# NB-IoT-ideaboard-v2_0.net
KiCad netlist of a schematic drawn in EAGLE
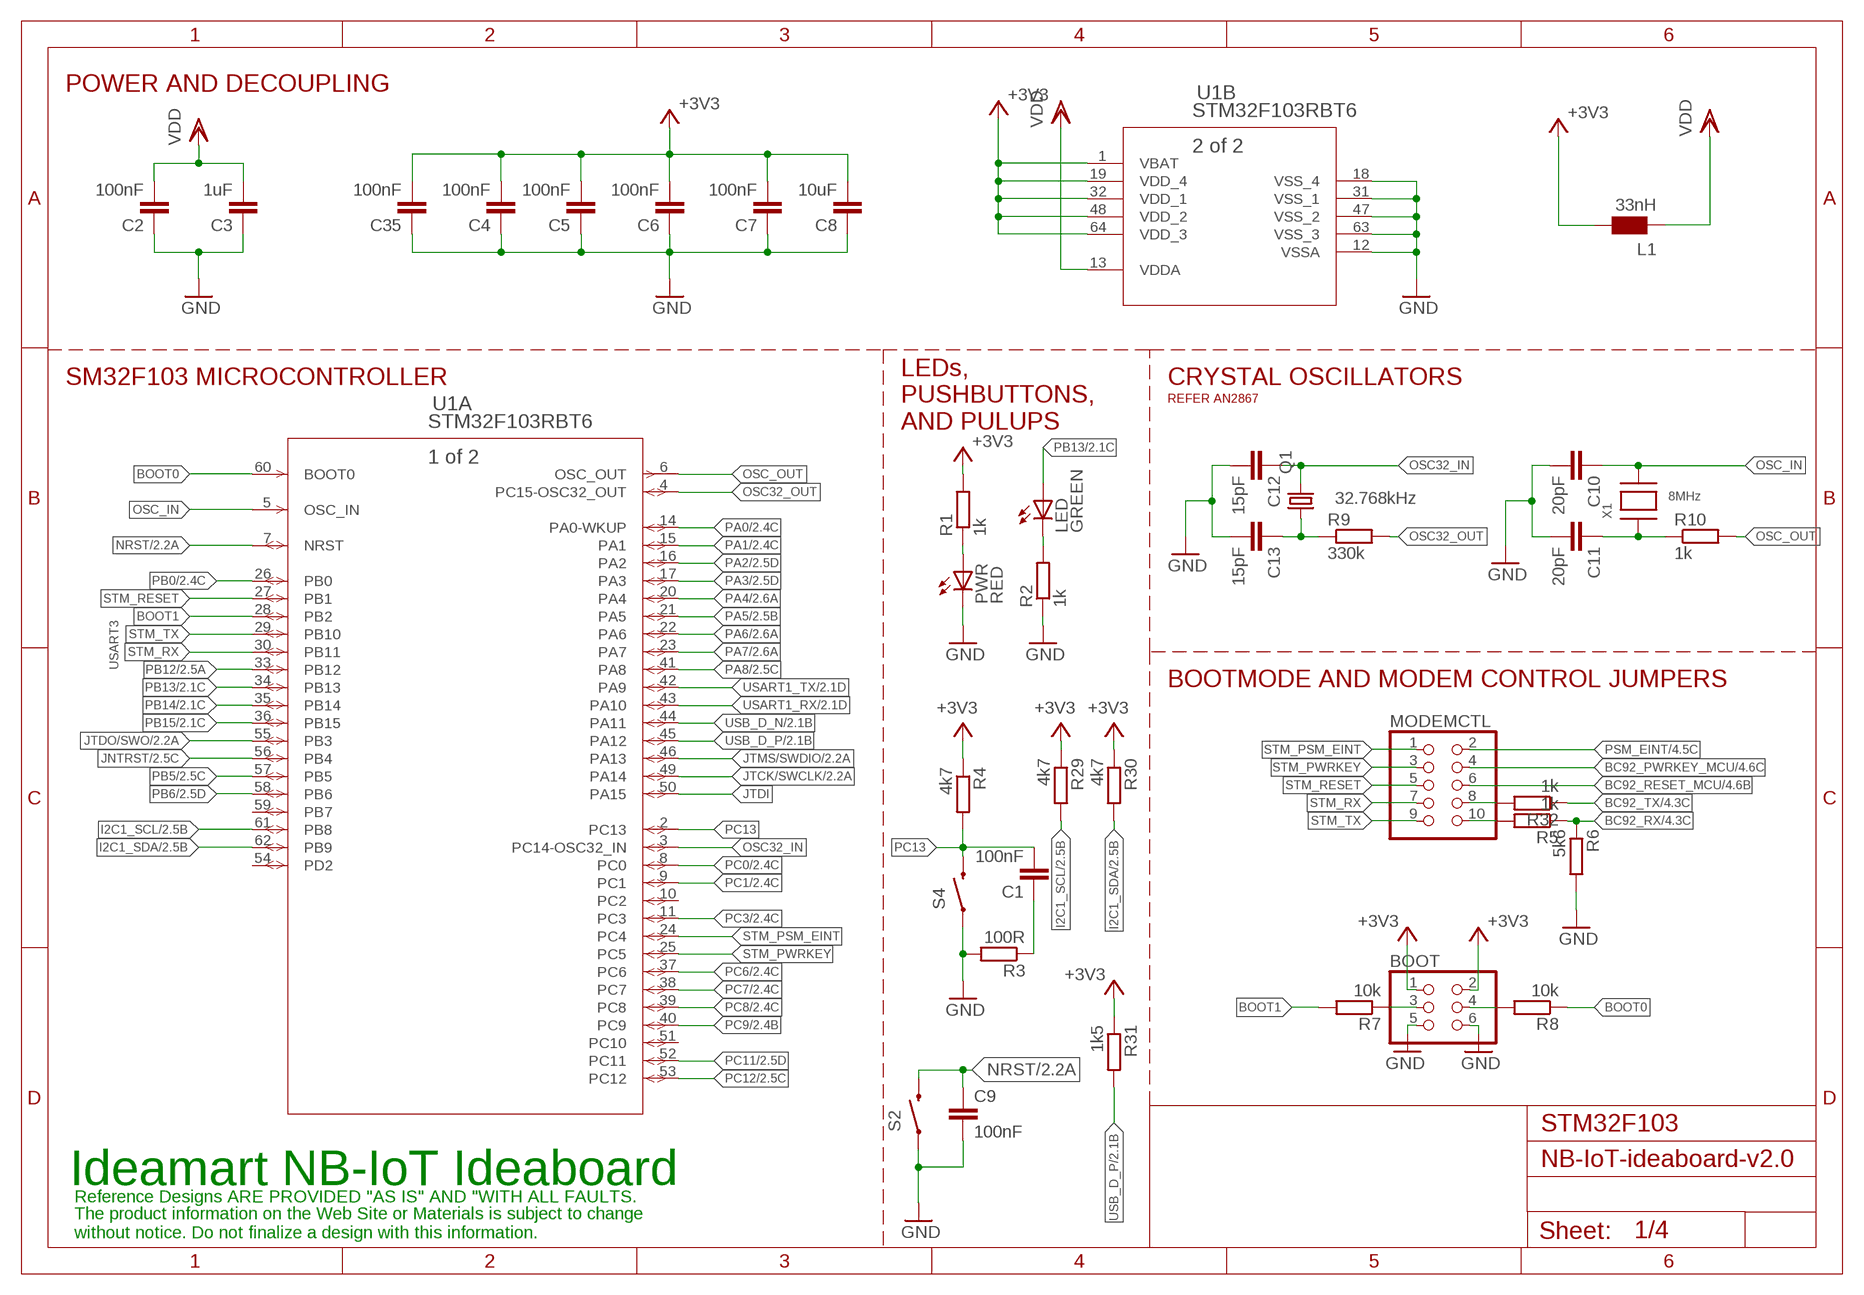
[diagram p0: schematic, sheet 1]
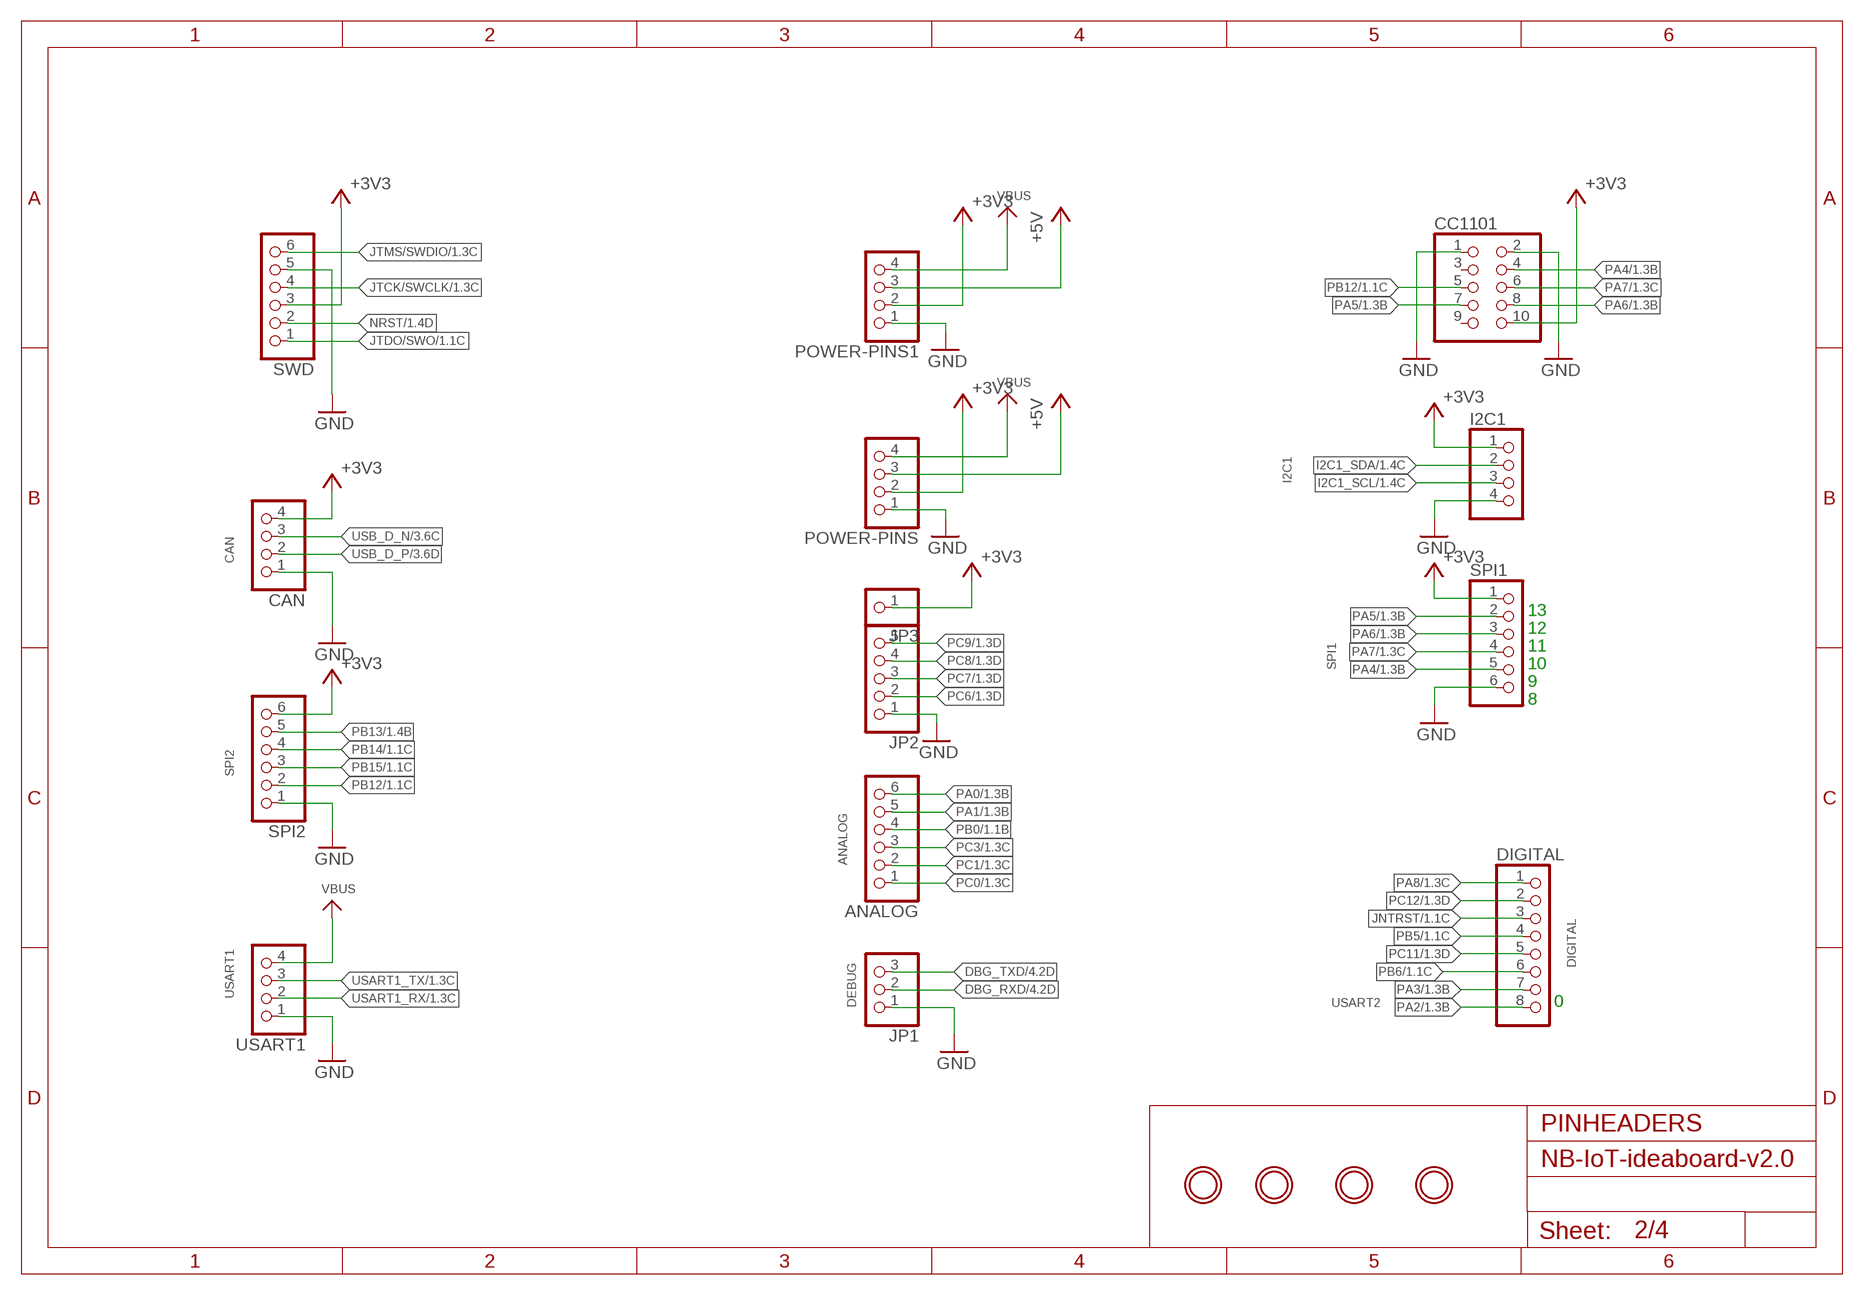
[diagram p1: schematic, sheet 2]
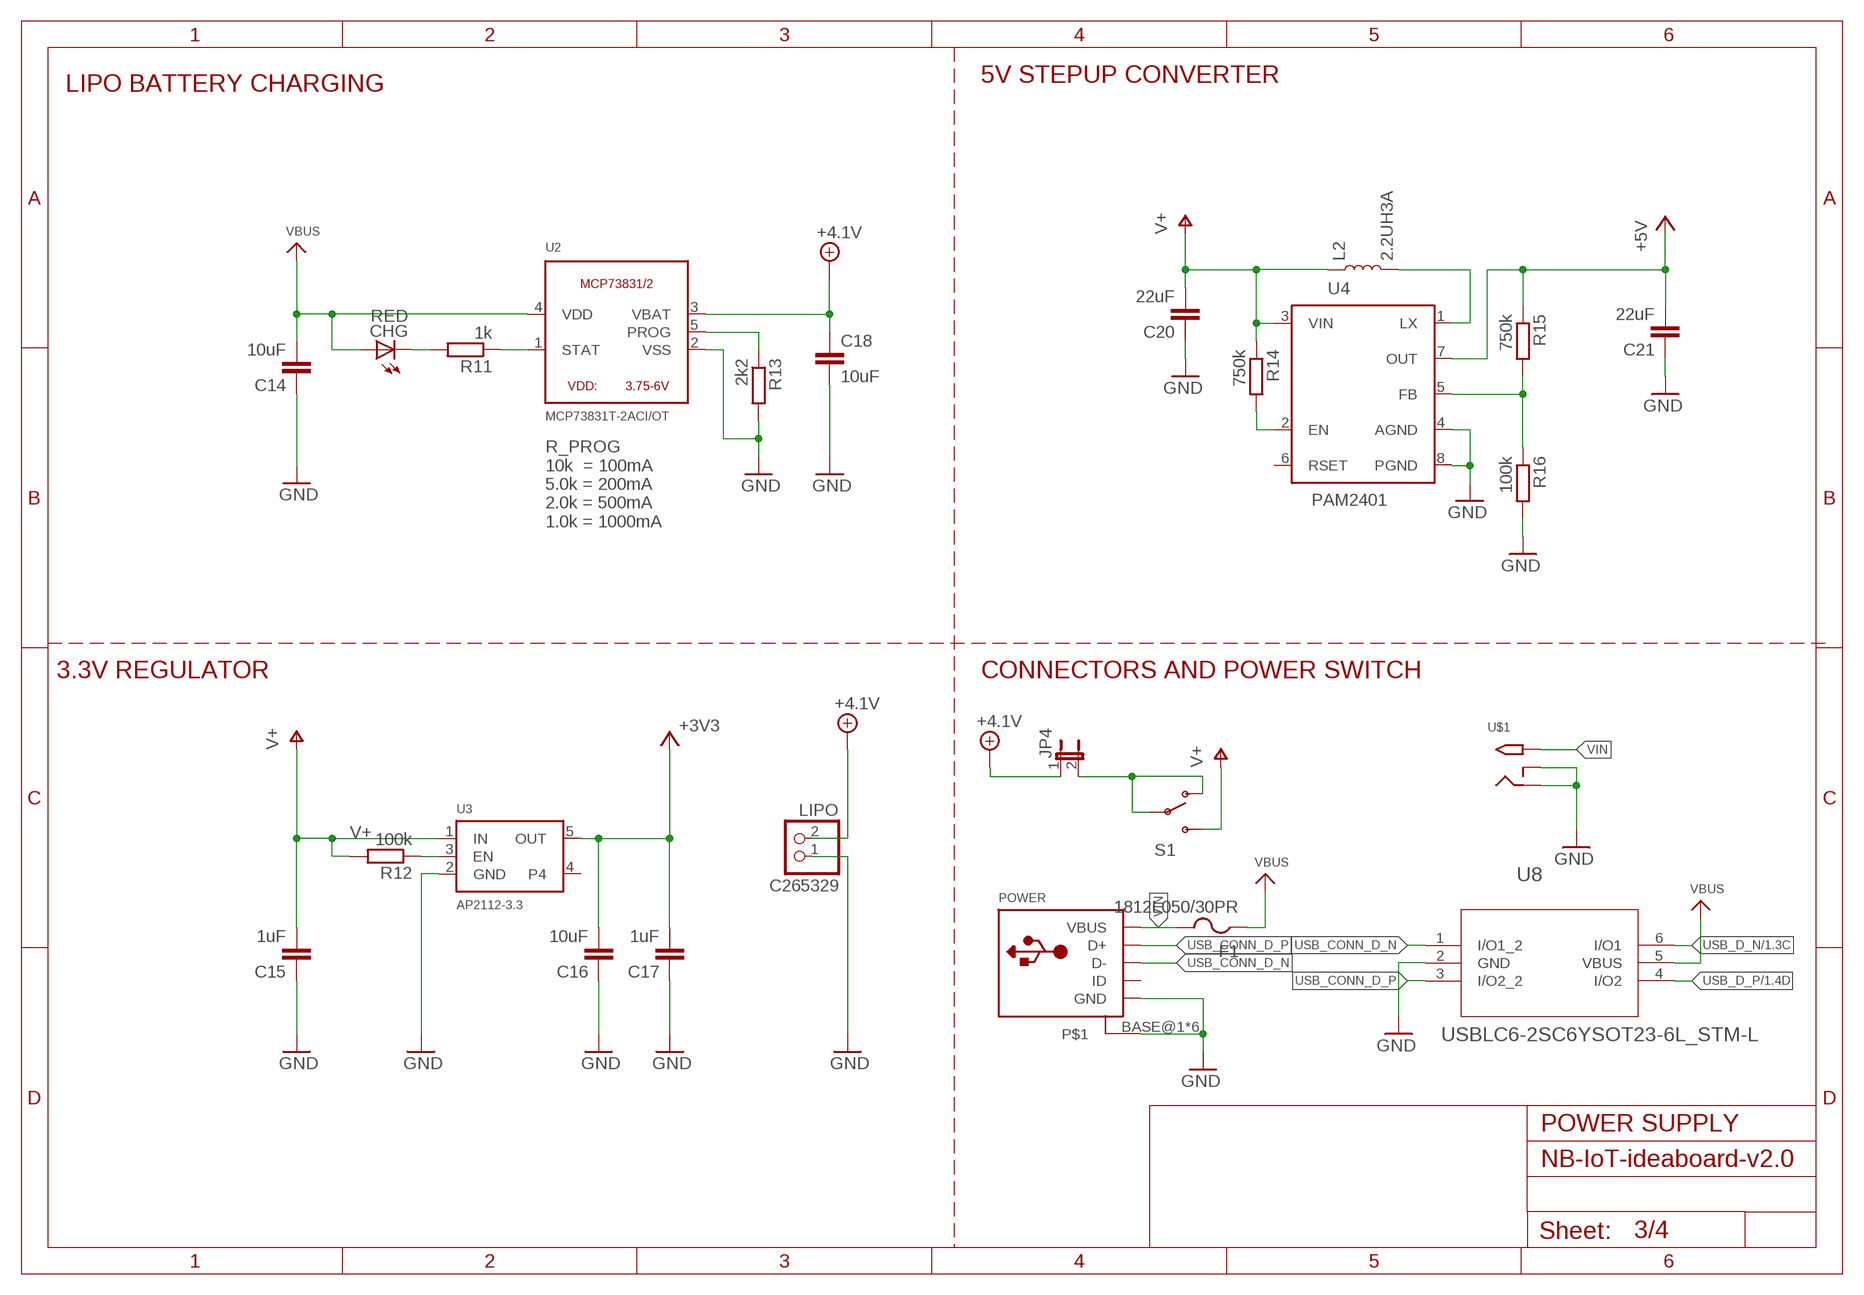
[diagram p2: schematic, sheet 3]
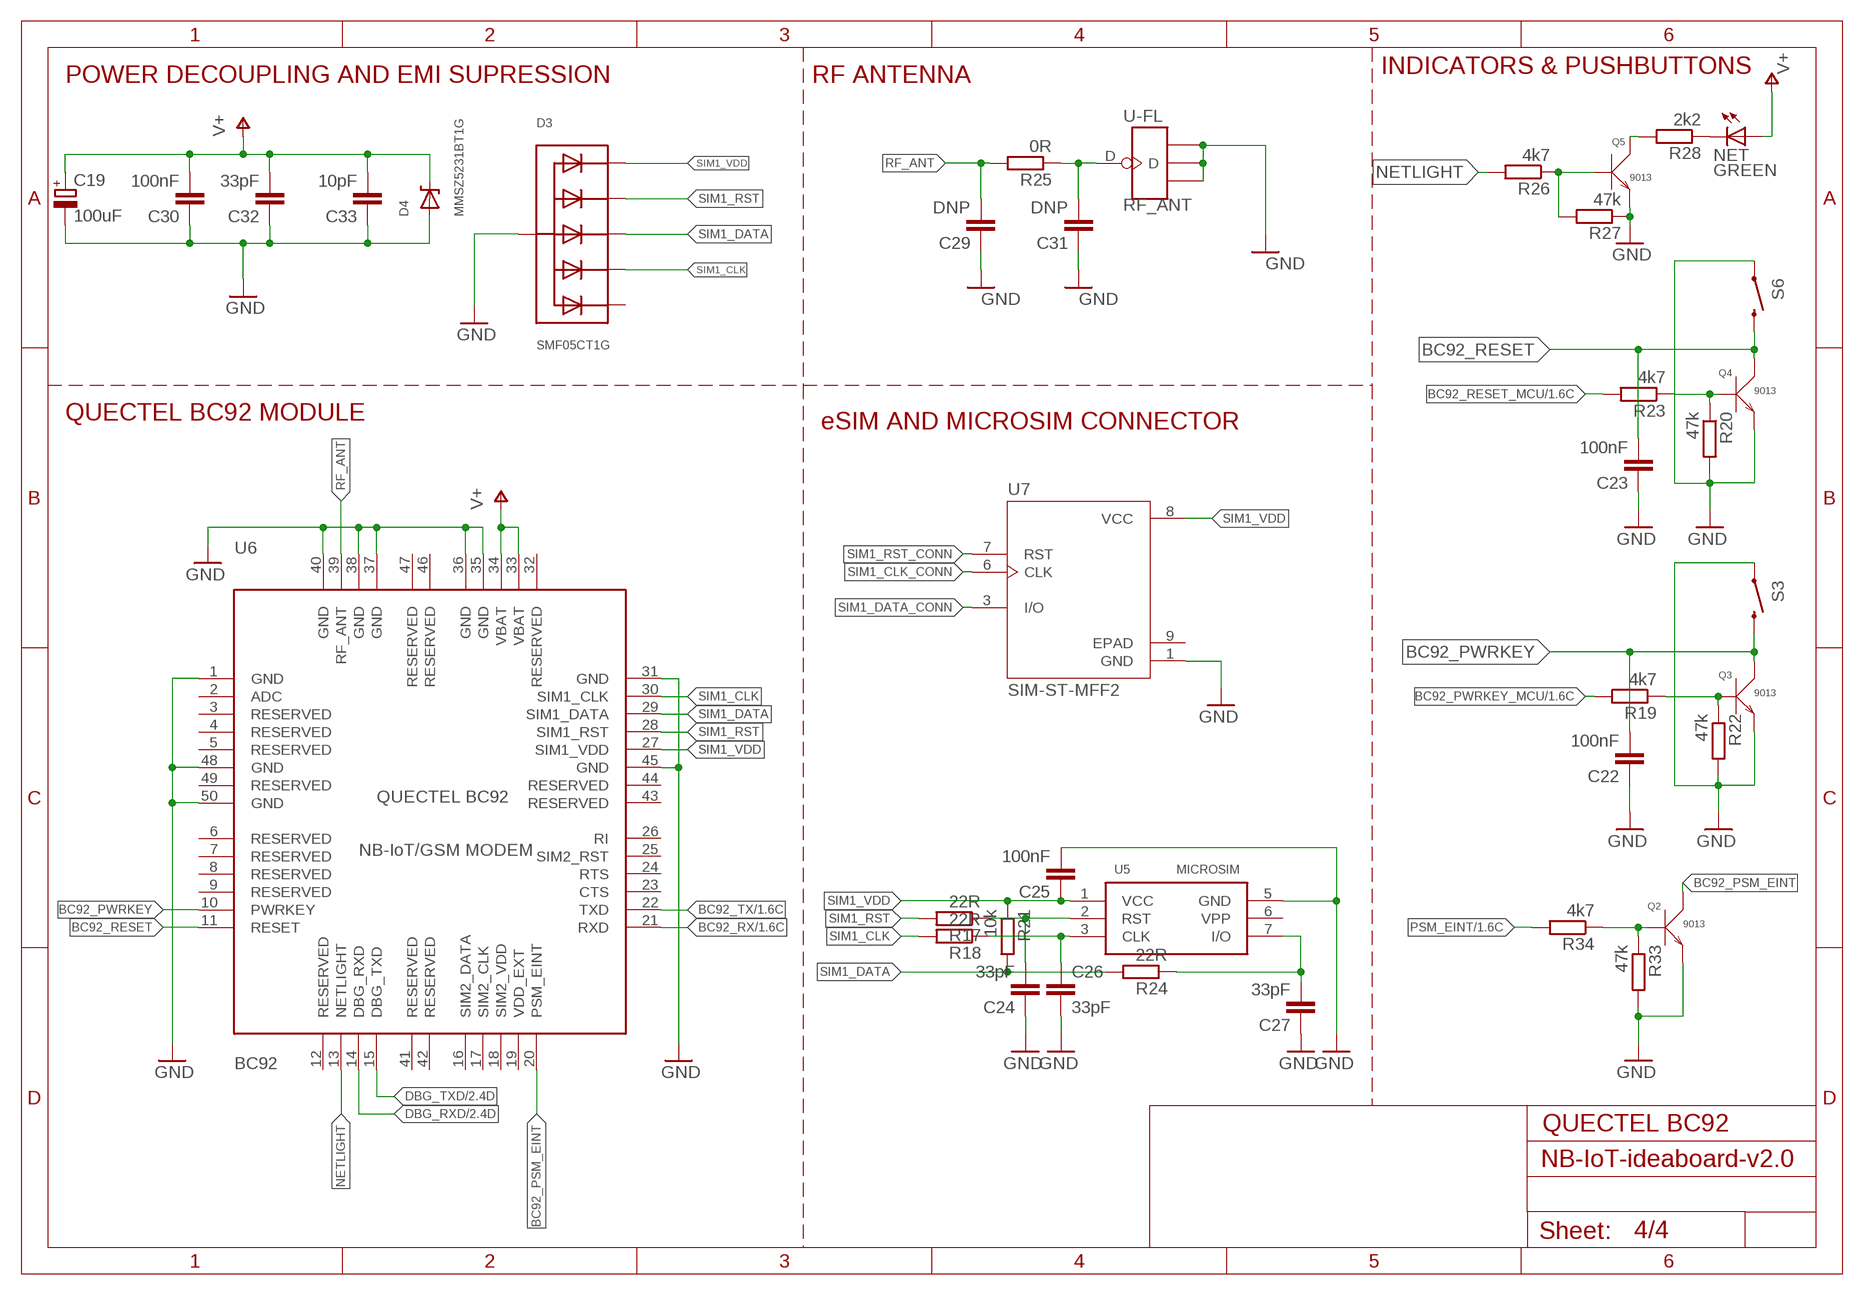
[diagram p3: schematic, sheet 4]

(export (version "E")
  (design (tool "Eeschema 10.0.6"))
  (components
    (comp (ref "$H1")
      (value "MOUNTINGHOLE3.0THIN")
      (footprint "eagle-import:MOUNTINGHOLE_3.0_PLATEDTHIN")
      (libsource (lib "eagle-import") (part "MOUNTINGHOLE3.0THIN"))
    )
    (comp (ref "$H2")
      (value "MOUNTINGHOLE3.0THIN")
      (footprint "eagle-import:MOUNTINGHOLE_3.0_PLATEDTHIN")
      (libsource (lib "eagle-import") (part "MOUNTINGHOLE3.0THIN"))
    )
    (comp (ref "$H3")
      (value "MOUNTINGHOLE3.0THIN")
      (footprint "eagle-import:MOUNTINGHOLE_3.0_PLATEDTHIN")
      (libsource (lib "eagle-import") (part "MOUNTINGHOLE3.0THIN"))
    )
    (comp (ref "$H4")
      (value "MOUNTINGHOLE3.0THIN")
      (footprint "eagle-import:MOUNTINGHOLE_3.0_PLATEDTHIN")
      (libsource (lib "eagle-import") (part "MOUNTINGHOLE3.0THIN"))
    )
    (comp (ref "ANALOG")
      (value "PINHD-1X06_2.54-S")
      (footprint "eagle-import:1X06-S")
      (libsource (lib "eagle-import") (part "PINHD-1X06_2.54-S"))
    )
    (comp (ref "CAN")
      (value "PINHD-1X04_2.54-S")
      (footprint "eagle-import:1X04-S")
      (libsource (lib "eagle-import") (part "PINHD-1X04_2.54-S"))
    )
    (comp (ref "CC1101")
      (value "PINHD-2X05_2.54")
      (footprint "eagle-import:2X05")
      (libsource (lib "eagle-import") (part "PINHD-2X05_2.54"))
    )
    (comp (ref "DIGITAL")
      (value "PINHD-1X08_2.54-S")
      (footprint "eagle-import:1X08-S")
      (libsource (lib "eagle-import") (part "PINHD-1X08_2.54-S"))
    )
    (comp (ref "I2C1")
      (value "PINHD-1X04_2.54-S")
      (footprint "eagle-import:1X04-S")
      (libsource (lib "eagle-import") (part "PINHD-1X04_2.54-S"))
    )
    (comp (ref "JP1")
      (value "PINHD-1X03_2.54-S")
      (footprint "eagle-import:1X03-S")
      (libsource (lib "eagle-import") (part "PINHD-1X03_2.54-S"))
    )
    (comp (ref "JP2")
      (value "PINHD-1X05_2.54-S")
      (footprint "eagle-import:1X05-S")
      (libsource (lib "eagle-import") (part "PINHD-1X05_2.54-S"))
    )
    (comp (ref "JP3")
      (value "PINHD-1X01_2.54-S")
      (footprint "eagle-import:1X01-S")
      (libsource (lib "eagle-import") (part "PINHD-1X01_2.54-S"))
    )
    (comp (ref "POWER-PINS")
      (value "PINHD-1X04_2.54-S")
      (footprint "eagle-import:1X04-S")
      (libsource (lib "eagle-import") (part "PINHD-1X04_2.54-S"))
    )
    (comp (ref "POWER-PINS1")
      (value "PINHD-1X04_2.54-S")
      (footprint "eagle-import:1X04-S")
      (libsource (lib "eagle-import") (part "PINHD-1X04_2.54-S"))
    )
    (comp (ref "SPI1")
      (value "PINHD-1X06_2.54-S")
      (footprint "eagle-import:1X06-S")
      (libsource (lib "eagle-import") (part "PINHD-1X06_2.54-S"))
    )
    (comp (ref "SPI2")
      (value "PINHD-1X06_2.54-S")
      (footprint "eagle-import:1X06-S")
      (libsource (lib "eagle-import") (part "PINHD-1X06_2.54-S"))
    )
    (comp (ref "SWD")
      (value "PINHD-1X06_2.54-S")
      (footprint "eagle-import:1X06-S")
      (libsource (lib "eagle-import") (part "PINHD-1X06_2.54-S"))
    )
    (comp (ref "USART1")
      (value "PINHD-1X04_2.54-S")
      (footprint "eagle-import:1X04-S")
      (libsource (lib "eagle-import") (part "PINHD-1X04_2.54-S"))
    )
    (comp (ref "BOOT")
      (value "PINHD-2X03_2.54")
      (footprint "eagle-import:2X03")
      (libsource (lib "eagle-import") (part "PINHD-2X03_2.54"))
    )
    (comp (ref "C1")
      (value "100nF")
      (footprint "eagle-import:C0805")
      (libsource (lib "eagle-import") (part "C-EUC0805"))
    )
    (comp (ref "C2")
      (value "100nF")
      (footprint "eagle-import:C0805")
      (libsource (lib "eagle-import") (part "C-EUC0805"))
    )
    (comp (ref "C3")
      (value "1uF")
      (footprint "eagle-import:C0805")
      (libsource (lib "eagle-import") (part "C-EUC0805"))
    )
    (comp (ref "C4")
      (value "100nF")
      (footprint "eagle-import:C0805")
      (libsource (lib "eagle-import") (part "C-EUC0805"))
    )
    (comp (ref "C5")
      (value "100nF")
      (footprint "eagle-import:C0805")
      (libsource (lib "eagle-import") (part "C-EUC0805"))
    )
    (comp (ref "C6")
      (value "100nF")
      (footprint "eagle-import:C0805")
      (libsource (lib "eagle-import") (part "C-EUC0805"))
    )
    (comp (ref "C7")
      (value "100nF")
      (footprint "eagle-import:C0805")
      (libsource (lib "eagle-import") (part "C-EUC0805"))
    )
    (comp (ref "C8")
      (value "10uF")
      (footprint "eagle-import:C1206")
      (libsource (lib "eagle-import") (part "C-EUC1206"))
    )
    (comp (ref "C9")
      (value "100nF")
      (footprint "eagle-import:C0805")
      (libsource (lib "eagle-import") (part "C-EUC0805"))
    )
    (comp (ref "C10")
      (value "20pF")
      (footprint "eagle-import:C0805")
      (libsource (lib "eagle-import") (part "C-EUC0805"))
    )
    (comp (ref "C11")
      (value "20pF")
      (footprint "eagle-import:C0805")
      (libsource (lib "eagle-import") (part "C-EUC0805"))
    )
    (comp (ref "C12")
      (value "15pF")
      (footprint "eagle-import:C0805")
      (libsource (lib "eagle-import") (part "C-EUC0805"))
    )
    (comp (ref "C13")
      (value "15pF")
      (footprint "eagle-import:C0805")
      (libsource (lib "eagle-import") (part "C-EUC0805"))
    )
    (comp (ref "C35")
      (value "100nF")
      (footprint "eagle-import:C0805")
      (libsource (lib "eagle-import") (part "C-EUC0805"))
    )
    (comp (ref "L1")
      (value "33nH")
      (footprint "eagle-import:0603")
      (libsource (lib "eagle-import") (part "WE-CBF_0603"))
    )
    (comp (ref "LED")
      (value "GREEN")
      (footprint "eagle-import:CHIP-LED0805")
      (libsource (lib "eagle-import") (part "LEDCHIP-LED0805"))
    )
    (comp (ref "MODEMCTL")
      (value "PINHD-2X05_2.54")
      (footprint "eagle-import:2X05")
      (libsource (lib "eagle-import") (part "PINHD-2X05_2.54"))
    )
    (comp (ref "PWR")
      (value "RED")
      (footprint "eagle-import:CHIP-LED0805")
      (libsource (lib "eagle-import") (part "LEDCHIP-LED0805"))
    )
    (comp (ref "Q1")
      (value "32.768kHz")
      (footprint "eagle-import:3.2X1.5")
      (libsource (lib "eagle-import") (part "KX-327-NHT"))
    )
    (comp (ref "R1")
      (value "1k")
      (footprint "eagle-import:R0805")
      (libsource (lib "eagle-import") (part "R-EU_R0805"))
    )
    (comp (ref "R2")
      (value "1k")
      (footprint "eagle-import:R0805")
      (libsource (lib "eagle-import") (part "R-EU_R0805"))
    )
    (comp (ref "R3")
      (value "100R")
      (footprint "eagle-import:R0805")
      (libsource (lib "eagle-import") (part "R-EU_R0805"))
    )
    (comp (ref "R4")
      (value "4k7")
      (footprint "eagle-import:R0805")
      (libsource (lib "eagle-import") (part "R-EU_R0805"))
    )
    (comp (ref "R5")
      (value "1k")
      (footprint "eagle-import:R0805")
      (libsource (lib "eagle-import") (part "R-EU_R0805"))
    )
    (comp (ref "R6")
      (value "5k6")
      (footprint "eagle-import:R0805")
      (libsource (lib "eagle-import") (part "R-EU_R0805"))
    )
    (comp (ref "R7")
      (value "10k")
      (footprint "eagle-import:R0805")
      (libsource (lib "eagle-import") (part "R-EU_R0805"))
    )
    (comp (ref "R8")
      (value "10k")
      (footprint "eagle-import:R0805")
      (libsource (lib "eagle-import") (part "R-EU_R0805"))
    )
    (comp (ref "R9")
      (value "330k")
      (footprint "eagle-import:R0805")
      (libsource (lib "eagle-import") (part "R-EU_R0805"))
    )
    (comp (ref "R10")
      (value "1k")
      (footprint "eagle-import:R0805")
      (libsource (lib "eagle-import") (part "R-EU_R0805"))
    )
    (comp (ref "R29")
      (value "4k7")
      (footprint "eagle-import:R0805")
      (libsource (lib "eagle-import") (part "R-EU_R0805"))
    )
    (comp (ref "R30")
      (value "4k7")
      (footprint "eagle-import:R0805")
      (libsource (lib "eagle-import") (part "R-EU_R0805"))
    )
    (comp (ref "R31")
      (value "1k5")
      (footprint "eagle-import:R0805")
      (libsource (lib "eagle-import") (part "R-EU_R0805"))
    )
    (comp (ref "R32")
      (value "1k")
      (footprint "eagle-import:R0805")
      (libsource (lib "eagle-import") (part "R-EU_R0805"))
    )
    (comp (ref "S2")
      (value "SWITCH-MOMENTARY-2SMD")
      (footprint "eagle-import:TACTILE-SWITCH-SMD")
      (libsource (lib "eagle-import") (part "SWITCH-MOMENTARY-2SMD"))
    )
    (comp (ref "S4")
      (value "SWITCH-MOMENTARY-2SMD")
      (footprint "eagle-import:TACTILE-SWITCH-SMD")
      (libsource (lib "eagle-import") (part "SWITCH-MOMENTARY-2SMD"))
    )
    (comp (ref "U1")
      (value "STM32F103RBT6")
      (footprint "eagle-import:LQFP64-10X10MM")
      (fields (field (name "COPYRIGHT") "Copyright (C) 2018 Accelerated Designs. All rights reserved"))
      (libsource (lib "eagle-import") (part "STM32F103RBT6"))
    )
    (comp (ref "X1")
      (value "8MHz")
      (footprint "eagle-import:NX5032")
      (libsource (lib "eagle-import") (part "XTALNX5032"))
    )
    (comp (ref "C19")
      (value "100uF")
      (footprint "eagle-import:B_3528-21R")
      (libsource (lib "eagle-import") (part "CPOL-EUB/3528-21R"))
    )
    (comp (ref "C22")
      (value "100nF")
      (footprint "eagle-import:C0805")
      (libsource (lib "eagle-import") (part "C-EUC0805"))
    )
    (comp (ref "C23")
      (value "100nF")
      (footprint "eagle-import:C0805")
      (libsource (lib "eagle-import") (part "C-EUC0805"))
    )
    (comp (ref "C24")
      (value "33pF")
      (footprint "eagle-import:C0805")
      (libsource (lib "eagle-import") (part "C-EUC0805"))
    )
    (comp (ref "C25")
      (value "100nF")
      (footprint "eagle-import:C0805")
      (libsource (lib "eagle-import") (part "C-EUC0805"))
    )
    (comp (ref "C26")
      (value "33pF")
      (footprint "eagle-import:C0805")
      (libsource (lib "eagle-import") (part "C-EUC0805"))
    )
    (comp (ref "C27")
      (value "33pF")
      (footprint "eagle-import:C0805")
      (libsource (lib "eagle-import") (part "C-EUC0805"))
    )
    (comp (ref "C29")
      (value "DNP")
      (footprint "eagle-import:C0805")
      (libsource (lib "eagle-import") (part "C-EUC0805"))
    )
    (comp (ref "C30")
      (value "100nF")
      (footprint "eagle-import:C0805")
      (libsource (lib "eagle-import") (part "C-EUC0805"))
    )
    (comp (ref "C31")
      (value "DNP")
      (footprint "eagle-import:C0805")
      (libsource (lib "eagle-import") (part "C-EUC0805"))
    )
    (comp (ref "C32")
      (value "33pF")
      (footprint "eagle-import:C0805")
      (libsource (lib "eagle-import") (part "C-EUC0805"))
    )
    (comp (ref "C33")
      (value "10pF")
      (footprint "eagle-import:C0805")
      (libsource (lib "eagle-import") (part "C-EUC0805"))
    )
    (comp (ref "D3")
      (value "SMF05CT1G")
      (footprint "eagle-import:SOT363")
      (libsource (lib "eagle-import") (part "TVSARRAY_5LANE"))
    )
    (comp (ref "D4")
      (value "MMSZ5231BT1G")
      (footprint "eagle-import:SOD-123")
      (libsource (lib "eagle-import") (part "DIODE-ZENERSOD123"))
    )
    (comp (ref "NET")
      (value "GREEN")
      (footprint "eagle-import:CHIP-LED0805")
      (libsource (lib "eagle-import") (part "LEDCHIP-LED0805"))
    )
    (comp (ref "Q2")
      (value "9013")
      (footprint "eagle-import:SOT23")
      (libsource (lib "eagle-import") (part "TRANSISTOR-NPN-SOT23"))
    )
    (comp (ref "Q3")
      (value "9013")
      (footprint "eagle-import:SOT23")
      (libsource (lib "eagle-import") (part "TRANSISTOR-NPN-SOT23"))
    )
    (comp (ref "Q4")
      (value "9013")
      (footprint "eagle-import:SOT23")
      (libsource (lib "eagle-import") (part "TRANSISTOR-NPN-SOT23"))
    )
    (comp (ref "Q5")
      (value "9013")
      (footprint "eagle-import:SOT23")
      (libsource (lib "eagle-import") (part "TRANSISTOR-NPN-SOT23"))
    )
    (comp (ref "R17")
      (value "22R")
      (footprint "eagle-import:R0805")
      (libsource (lib "eagle-import") (part "R-EU_R0805"))
    )
    (comp (ref "R18")
      (value "22R")
      (footprint "eagle-import:R0805")
      (libsource (lib "eagle-import") (part "R-EU_R0805"))
    )
    (comp (ref "R19")
      (value "4k7")
      (footprint "eagle-import:R0805")
      (libsource (lib "eagle-import") (part "R-EU_R0805"))
    )
    (comp (ref "R20")
      (value "47k")
      (footprint "eagle-import:R0805")
      (libsource (lib "eagle-import") (part "R-EU_R0805"))
    )
    (comp (ref "R21")
      (value "10k")
      (footprint "eagle-import:R0805")
      (libsource (lib "eagle-import") (part "R-EU_R0805"))
    )
    (comp (ref "R22")
      (value "47k")
      (footprint "eagle-import:R0805")
      (libsource (lib "eagle-import") (part "R-EU_R0805"))
    )
    (comp (ref "R23")
      (value "4k7")
      (footprint "eagle-import:R0805")
      (libsource (lib "eagle-import") (part "R-EU_R0805"))
    )
    (comp (ref "R24")
      (value "22R")
      (footprint "eagle-import:R0805")
      (libsource (lib "eagle-import") (part "R-EU_R0805"))
    )
    (comp (ref "R25")
      (value "0R")
      (footprint "eagle-import:R0805")
      (libsource (lib "eagle-import") (part "R-EU_R0805"))
    )
    (comp (ref "R26")
      (value "4k7")
      (footprint "eagle-import:R0805")
      (libsource (lib "eagle-import") (part "R-EU_R0805"))
    )
    (comp (ref "R27")
      (value "47k")
      (footprint "eagle-import:R0805")
      (libsource (lib "eagle-import") (part "R-EU_R0805"))
    )
    (comp (ref "R28")
      (value "2k2")
      (footprint "eagle-import:R0805")
      (libsource (lib "eagle-import") (part "R-EU_R0805"))
    )
    (comp (ref "R33")
      (value "47k")
      (footprint "eagle-import:R0805")
      (libsource (lib "eagle-import") (part "R-EU_R0805"))
    )
    (comp (ref "R34")
      (value "4k7")
      (footprint "eagle-import:R0805")
      (libsource (lib "eagle-import") (part "R-EU_R0805"))
    )
    (comp (ref "RF_ANT")
      (value "U-FL")
      (footprint "eagle-import:4P-U-FL")
      (libsource (lib "eagle-import") (part "ANTENNA-U-FL"))
    )
    (comp (ref "S3")
      (value "SWITCH-MOMENTARY-2SMD")
      (footprint "eagle-import:TACTILE-SWITCH-SMD")
      (libsource (lib "eagle-import") (part "SWITCH-MOMENTARY-2SMD"))
    )
    (comp (ref "S6")
      (value "SWITCH-MOMENTARY-2SMD")
      (footprint "eagle-import:TACTILE-SWITCH-SMD")
      (libsource (lib "eagle-import") (part "SWITCH-MOMENTARY-2SMD"))
    )
    (comp (ref "U5")
      (value "MICROSIM")
      (footprint "eagle-import:MICROSIM")
      (libsource (lib "eagle-import") (part "MICROSIM"))
    )
    (comp (ref "U6")
      (value "BC92")
      (footprint "eagle-import:BC92")
      (libsource (lib "eagle-import") (part "BC92"))
    )
    (comp (ref "U7")
      (value "SIM-ST-MFF2")
      (footprint "eagle-import:PSON127P500X600X82-9N")
      (fields (field (name "MF") "Hologram, Inc."))
      (libsource (lib "eagle-import") (part "SIM-ST-MFF2"))
    )
    (comp (ref "C14")
      (value "10uF")
      (footprint "eagle-import:C0805")
      (libsource (lib "eagle-import") (part "C-EUC0805"))
    )
    (comp (ref "C15")
      (value "1uF")
      (footprint "eagle-import:C0805")
      (libsource (lib "eagle-import") (part "C-EUC0805"))
    )
    (comp (ref "C16")
      (value "10uF")
      (footprint "eagle-import:C0805")
      (libsource (lib "eagle-import") (part "C-EUC0805"))
    )
    (comp (ref "C17")
      (value "1uF")
      (footprint "eagle-import:C0805")
      (libsource (lib "eagle-import") (part "C-EUC0805"))
    )
    (comp (ref "C18")
      (value "10uF")
      (footprint "eagle-import:C0805")
      (libsource (lib "eagle-import") (part "C-EUC0805"))
    )
    (comp (ref "C20")
      (value "22uF")
      (footprint "eagle-import:C0805")
      (libsource (lib "eagle-import") (part "C-EUC0805"))
    )
    (comp (ref "C21")
      (value "22uF")
      (footprint "eagle-import:C0805")
      (libsource (lib "eagle-import") (part "C-EUC0805"))
    )
    (comp (ref "CHG")
      (value "RED")
      (footprint "eagle-import:CHIP-LED0805")
      (libsource (lib "eagle-import") (part "LEDCHIP-LED0805"))
    )
    (comp (ref "F1")
      (value "1812L050/30PR")
      (footprint "eagle-import:1812")
      (libsource (lib "eagle-import") (part "PTCFUSE-1812"))
    )
    (comp (ref "JP4")
      (value "JP1E")
      (footprint "eagle-import:JP1")
      (libsource (lib "eagle-import") (part "JP1E"))
    )
    (comp (ref "L2")
      (value "2.2UH3A")
      (footprint "eagle-import:INDUCTOR_4X4MM")
      (libsource (lib "eagle-import") (part "INDUCTOR-IFSC1515AHER2R2M01"))
    )
    (comp (ref "LIPO")
      (value "C265329")
      (footprint "eagle-import:JST-PH-2-SMT")
      (libsource (lib "eagle-import") (part "JST_2PIN-SMT"))
    )
    (comp (ref "POWER")
      (value "USB_MICRO_20329_V2")
      (footprint "eagle-import:4UCONN_20329_V2")
      (libsource (lib "eagle-import") (part "USB_MICRO_20329_V2"))
    )
    (comp (ref "R11")
      (value "1k")
      (footprint "eagle-import:R0805")
      (libsource (lib "eagle-import") (part "R-EU_R0805"))
    )
    (comp (ref "R12")
      (value "100k")
      (footprint "eagle-import:R0805")
      (libsource (lib "eagle-import") (part "R-EU_R0805"))
    )
    (comp (ref "R13")
      (value "2k2")
      (footprint "eagle-import:R0805")
      (libsource (lib "eagle-import") (part "R-EU_R0805"))
    )
    (comp (ref "R14")
      (value "750k")
      (footprint "eagle-import:R0805")
      (libsource (lib "eagle-import") (part "R-EU_R0805"))
    )
    (comp (ref "R15")
      (value "750k")
      (footprint "eagle-import:R0805")
      (libsource (lib "eagle-import") (part "R-EU_R0805"))
    )
    (comp (ref "R16")
      (value "100k")
      (footprint "eagle-import:R0805")
      (libsource (lib "eagle-import") (part "R-EU_R0805"))
    )
    (comp (ref "S1")
      (value "SWITCH-SPDT-SMD-A")
      (footprint "eagle-import:SWITCH-SPST-SMD-A")
      (libsource (lib "eagle-import") (part "SWITCH-SPDT-SMD-A"))
    )
    (comp (ref "U$1")
      (value "2.1MMJACKSMT")
      (footprint "eagle-import:DCJACK_2MM_SMT")
      (libsource (lib "eagle-import") (part "2.1MMJACKSMT"))
    )
    (comp (ref "U2")
      (value "MCP73831T-2ACI/OT")
      (footprint "eagle-import:SOT23-5")
      (libsource (lib "eagle-import") (part "MCP73831/2"))
    )
    (comp (ref "U3")
      (value "AP2112-3.3")
      (footprint "eagle-import:SOT23-5")
      (libsource (lib "eagle-import") (part "VREG_SOT23-5"))
    )
    (comp (ref "U4")
      (value "PAM2401")
      (footprint "eagle-import:MSOP8")
      (libsource (lib "eagle-import") (part "PAM2401"))
    )
    (comp (ref "U8")
      (value "USBLC6-2SC6YSOT23-6L_STM-L")
      (footprint "eagle-import:SOT23-6L_STM-L")
      (fields (field (name "MANUFACTURER_PART_NUMBER") "USBLC6-2SC6Y"))
      (libsource (lib "eagle-import") (part "USBLC6-2SC6YSOT23-6L_STM-L"))
    )
  )
  (nets
    (net (code "1") (name "+3V3") (class "Default")
      (node (ref "BOOT") (pin "1") (pinfunction "1_1") (pintype "passive"))
      (node (ref "BOOT") (pin "2") (pinfunction "2_2") (pintype "passive"))
      (node (ref "C16") (pin "2") (pinfunction "2_2") (pintype "passive"))
      (node (ref "C17") (pin "2") (pinfunction "2_2") (pintype "passive"))
      (node (ref "C35") (pin "2") (pinfunction "2_2") (pintype "passive"))
      (node (ref "C4") (pin "2") (pinfunction "2_2") (pintype "passive"))
      (node (ref "C5") (pin "2") (pinfunction "2_2") (pintype "passive"))
      (node (ref "C6") (pin "2") (pinfunction "2_2") (pintype "passive"))
      (node (ref "C7") (pin "2") (pinfunction "2_2") (pintype "passive"))
      (node (ref "C8") (pin "2") (pinfunction "2_2") (pintype "passive"))
      (node (ref "CAN") (pin "4") (pinfunction "4_4") (pintype "passive"))
      (node (ref "CC1101") (pin "10") (pinfunction "10_10") (pintype "passive"))
      (node (ref "I2C1") (pin "1") (pinfunction "1_1") (pintype "passive"))
      (node (ref "JP3") (pin "1") (pinfunction "1_1") (pintype "passive"))
      (node (ref "L1") (pin "2") (pinfunction "2_2") (pintype "passive"))
      (node (ref "POWER-PINS") (pin "2") (pinfunction "2_2") (pintype "passive"))
      (node (ref "POWER-PINS1") (pin "2") (pinfunction "2_2") (pintype "passive"))
      (node (ref "R1") (pin "2") (pinfunction "2_2") (pintype "passive"))
      (node (ref "R29") (pin "1") (pinfunction "1_1") (pintype "passive"))
      (node (ref "R30") (pin "1") (pinfunction "1_1") (pintype "passive"))
      (node (ref "R31") (pin "1") (pinfunction "1_1") (pintype "passive"))
      (node (ref "R4") (pin "1") (pinfunction "1_1") (pintype "passive"))
      (node (ref "SPI1") (pin "1") (pinfunction "1_1") (pintype "passive"))
      (node (ref "SPI2") (pin "6") (pinfunction "6_6") (pintype "passive"))
      (node (ref "SWD") (pin "3") (pinfunction "3_3") (pintype "passive"))
      (node (ref "U1") (pin "1") (pinfunction "VBAT_1") (pintype "power_in"))
      (node (ref "U1") (pin "19") (pinfunction "VDD_4_19") (pintype "power_in"))
      (node (ref "U1") (pin "32") (pinfunction "VDD_1_32") (pintype "power_in"))
      (node (ref "U1") (pin "48") (pinfunction "VDD_2_48") (pintype "power_in"))
      (node (ref "U1") (pin "64") (pinfunction "VDD_3_64") (pintype "power_in"))
      (node (ref "U3") (pin "5") (pinfunction "OUT_5") (pintype "power_in"))
    )
    (net (code "2") (name "+4.1V") (class "Default")
      (node (ref "C18") (pin "1") (pinfunction "1_1") (pintype "passive"))
      (node (ref "JP4") (pin "1") (pinfunction "1_1") (pintype "passive"))
      (node (ref "LIPO") (pin "2") (pinfunction "1_2") (pintype "passive"))
      (node (ref "U2") (pin "3") (pinfunction "VBAT_3") (pintype "power_in"))
    )
    (net (code "3") (name "+5V") (class "Default")
      (node (ref "C21") (pin "2") (pinfunction "2_2") (pintype "passive"))
      (node (ref "POWER-PINS") (pin "3") (pinfunction "3_3") (pintype "passive"))
      (node (ref "POWER-PINS1") (pin "3") (pinfunction "3_3") (pintype "passive"))
      (node (ref "R15") (pin "1") (pinfunction "1_1") (pintype "passive"))
      (node (ref "U4") (pin "7") (pinfunction "OUT_7") (pintype "bidirectional"))
    )
    (net (code "4") (name "BC92_PSM_EINT") (class "Default")
      (node (ref "Q2") (pin "3") (pinfunction "C_3") (pintype "passive"))
      (node (ref "U6") (pin "20") (pinfunction "PSM_EINT_20") (pintype "bidirectional"))
    )
    (net (code "5") (name "BC92_PWRKEY") (class "Default")
      (node (ref "C22") (pin "2") (pinfunction "2_2") (pintype "passive"))
      (node (ref "Q3") (pin "3") (pinfunction "C_3") (pintype "passive"))
      (node (ref "S3") (pin "3") (pinfunction "2_3") (pintype "passive"))
      (node (ref "U6") (pin "10") (pinfunction "PWRKEY_10") (pintype "bidirectional"))
    )
    (net (code "6") (name "BC92_PWRKEY_MCU") (class "Default")
      (node (ref "MODEMCTL") (pin "4") (pinfunction "4_4") (pintype "passive"))
      (node (ref "R19") (pin "2") (pinfunction "2_2") (pintype "passive"))
    )
    (net (code "7") (name "BC92_RESET") (class "Default")
      (node (ref "C23") (pin "2") (pinfunction "2_2") (pintype "passive"))
      (node (ref "Q4") (pin "3") (pinfunction "C_3") (pintype "passive"))
      (node (ref "S6") (pin "3") (pinfunction "2_3") (pintype "passive"))
      (node (ref "U6") (pin "11") (pinfunction "RESET_11") (pintype "bidirectional"))
    )
    (net (code "8") (name "BC92_RESET_MCU") (class "Default")
      (node (ref "MODEMCTL") (pin "6") (pinfunction "6_6") (pintype "passive"))
      (node (ref "R23") (pin "2") (pinfunction "2_2") (pintype "passive"))
    )
    (net (code "9") (name "BC92_RX") (class "Default")
      (node (ref "R5") (pin "1") (pinfunction "1_1") (pintype "passive"))
      (node (ref "R6") (pin "1") (pinfunction "1_1") (pintype "passive"))
      (node (ref "U6") (pin "21") (pinfunction "RXD_21") (pintype "bidirectional"))
    )
    (net (code "10") (name "BC92_TX") (class "Default")
      (node (ref "R32") (pin "1") (pinfunction "1_1") (pintype "passive"))
      (node (ref "U6") (pin "22") (pinfunction "TXD_22") (pintype "bidirectional"))
    )
    (net (code "11") (name "BOOT0") (class "Default")
      (node (ref "R8") (pin "1") (pinfunction "1_1") (pintype "passive"))
      (node (ref "U1") (pin "60") (pinfunction "BOOT0_60") (pintype "input"))
    )
    (net (code "12") (name "BOOT1") (class "Default")
      (node (ref "R7") (pin "2") (pinfunction "2_2") (pintype "passive"))
      (node (ref "U1") (pin "28") (pinfunction "PB2_28") (pintype "bidirectional"))
    )
    (net (code "13") (name "DBG_RXD") (class "Default")
      (node (ref "JP1") (pin "2") (pinfunction "2_2") (pintype "passive"))
      (node (ref "U6") (pin "14") (pinfunction "DBG_RXD_14") (pintype "bidirectional"))
    )
    (net (code "14") (name "DBG_TXD") (class "Default")
      (node (ref "JP1") (pin "3") (pinfunction "3_3") (pintype "passive"))
      (node (ref "U6") (pin "15") (pinfunction "DBG_TXD_15") (pintype "bidirectional"))
    )
    (net (code "15") (name "GND") (class "Default")
      (node (ref "BOOT") (pin "5") (pinfunction "5_5") (pintype "passive"))
      (node (ref "BOOT") (pin "6") (pinfunction "6_6") (pintype "passive"))
      (node (ref "C10") (pin "2") (pinfunction "2_2") (pintype "passive"))
      (node (ref "C11") (pin "2") (pinfunction "2_2") (pintype "passive"))
      (node (ref "C12") (pin "2") (pinfunction "2_2") (pintype "passive"))
      (node (ref "C13") (pin "2") (pinfunction "2_2") (pintype "passive"))
      (node (ref "C14") (pin "1") (pinfunction "1_1") (pintype "passive"))
      (node (ref "C15") (pin "1") (pinfunction "1_1") (pintype "passive"))
      (node (ref "C16") (pin "1") (pinfunction "1_1") (pintype "passive"))
      (node (ref "C17") (pin "1") (pinfunction "1_1") (pintype "passive"))
      (node (ref "C18") (pin "2") (pinfunction "2_2") (pintype "passive"))
      (node (ref "C19") (pin "-") (pinfunction "-_-") (pintype "passive"))
      (node (ref "C2") (pin "1") (pinfunction "1_1") (pintype "passive"))
      (node (ref "C20") (pin "1") (pinfunction "1_1") (pintype "passive"))
      (node (ref "C21") (pin "1") (pinfunction "1_1") (pintype "passive"))
      (node (ref "C22") (pin "1") (pinfunction "1_1") (pintype "passive"))
      (node (ref "C23") (pin "1") (pinfunction "1_1") (pintype "passive"))
      (node (ref "C24") (pin "1") (pinfunction "1_1") (pintype "passive"))
      (node (ref "C25") (pin "2") (pinfunction "2_2") (pintype "passive"))
      (node (ref "C26") (pin "2") (pinfunction "2_2") (pintype "passive"))
      (node (ref "C27") (pin "1") (pinfunction "1_1") (pintype "passive"))
      (node (ref "C29") (pin "1") (pinfunction "1_1") (pintype "passive"))
      (node (ref "C3") (pin "1") (pinfunction "1_1") (pintype "passive"))
      (node (ref "C30") (pin "1") (pinfunction "1_1") (pintype "passive"))
      (node (ref "C31") (pin "1") (pinfunction "1_1") (pintype "passive"))
      (node (ref "C32") (pin "1") (pinfunction "1_1") (pintype "passive"))
      (node (ref "C33") (pin "1") (pinfunction "1_1") (pintype "passive"))
      (node (ref "C35") (pin "1") (pinfunction "1_1") (pintype "passive"))
      (node (ref "C4") (pin "1") (pinfunction "1_1") (pintype "passive"))
      (node (ref "C5") (pin "1") (pinfunction "1_1") (pintype "passive"))
      (node (ref "C6") (pin "1") (pinfunction "1_1") (pintype "passive"))
      (node (ref "C7") (pin "1") (pinfunction "1_1") (pintype "passive"))
      (node (ref "C8") (pin "1") (pinfunction "1_1") (pintype "passive"))
      (node (ref "C9") (pin "2") (pinfunction "2_2") (pintype "passive"))
      (node (ref "CAN") (pin "1") (pinfunction "1_1") (pintype "passive"))
      (node (ref "CC1101") (pin "1") (pinfunction "1_1") (pintype "passive"))
      (node (ref "CC1101") (pin "2") (pinfunction "2_2") (pintype "passive"))
      (node (ref "D3") (pin "2") (pinfunction "A_2") (pintype "passive"))
      (node (ref "D4") (pin "A") (pinfunction "A_A") (pintype "passive"))
      (node (ref "I2C1") (pin "4") (pinfunction "4_4") (pintype "passive"))
      (node (ref "JP1") (pin "1") (pinfunction "1_1") (pintype "passive"))
      (node (ref "JP2") (pin "1") (pinfunction "1_1") (pintype "passive"))
      (node (ref "LIPO") (pin "1") (pinfunction "2_1") (pintype "passive"))
      (node (ref "POWER") (pin "BASE@1") (pinfunction "P$1_BASE@1") (pintype "bidirectional"))
      (node (ref "POWER") (pin "BASE@2") (pinfunction "P$1_BASE@2") (pintype "bidirectional"))
      (node (ref "POWER") (pin "GND") (pinfunction "GND_GND") (pintype "power_in"))
      (node (ref "POWER") (pin "SPRT@1") (pinfunction "P$1_SPRT@1") (pintype "bidirectional"))
      (node (ref "POWER") (pin "SPRT@2") (pinfunction "P$1_SPRT@2") (pintype "bidirectional"))
      (node (ref "POWER") (pin "SPRT@3") (pinfunction "P$1_SPRT@3") (pintype "bidirectional"))
      (node (ref "POWER") (pin "SPRT@4") (pinfunction "P$1_SPRT@4") (pintype "bidirectional"))
      (node (ref "POWER-PINS") (pin "1") (pinfunction "1_1") (pintype "passive"))
      (node (ref "POWER-PINS1") (pin "1") (pinfunction "1_1") (pintype "passive"))
      (node (ref "PWR") (pin "C") (pinfunction "C_C") (pintype "passive"))
      (node (ref "Q2") (pin "2") (pinfunction "E_2") (pintype "passive"))
      (node (ref "Q3") (pin "2") (pinfunction "E_2") (pintype "passive"))
      (node (ref "Q4") (pin "2") (pinfunction "E_2") (pintype "passive"))
      (node (ref "Q5") (pin "2") (pinfunction "E_2") (pintype "passive"))
      (node (ref "R13") (pin "2") (pinfunction "2_2") (pintype "passive"))
      (node (ref "R16") (pin "2") (pinfunction "2_2") (pintype "passive"))
      (node (ref "R2") (pin "1") (pinfunction "1_1") (pintype "passive"))
      (node (ref "R20") (pin "2") (pinfunction "2_2") (pintype "passive"))
      (node (ref "R22") (pin "2") (pinfunction "2_2") (pintype "passive"))
      (node (ref "R27") (pin "1") (pinfunction "1_1") (pintype "passive"))
      (node (ref "R3") (pin "2") (pinfunction "2_2") (pintype "passive"))
      (node (ref "R33") (pin "2") (pinfunction "2_2") (pintype "passive"))
      (node (ref "R6") (pin "2") (pinfunction "2_2") (pintype "passive"))
      (node (ref "RF_ANT") (pin "GND1") (pinfunction "GND1_GND1") (pintype "bidirectional"))
      (node (ref "RF_ANT") (pin "GND2") (pinfunction "GND2_GND2") (pintype "bidirectional"))
      (node (ref "RF_ANT") (pin "GND3") (pinfunction "GND3_GND3") (pintype "bidirectional"))
      (node (ref "S2") (pin "1") (pinfunction "1_1") (pintype "passive"))
      (node (ref "S3") (pin "1") (pinfunction "1_1") (pintype "passive"))
      (node (ref "S4") (pin "1") (pinfunction "1_1") (pintype "passive"))
      (node (ref "S6") (pin "1") (pinfunction "1_1") (pintype "passive"))
      (node (ref "SPI1") (pin "6") (pinfunction "6_6") (pintype "passive"))
      (node (ref "SPI2") (pin "1") (pinfunction "1_1") (pintype "passive"))
      (node (ref "SWD") (pin "5") (pinfunction "5_5") (pintype "passive"))
      (node (ref "U$1") (pin "GND") (pinfunction "RING_GND") (pintype "bidirectional"))
      (node (ref "U$1") (pin "GNDBREAK") (pinfunction "RING_SW_GNDBREAK") (pintype "bidirectional"))
      (node (ref "U1") (pin "12") (pinfunction "VSSA_12") (pintype "power_in"))
      (node (ref "U1") (pin "18") (pinfunction "VSS_4_18") (pintype "power_in"))
      (node (ref "U1") (pin "31") (pinfunction "VSS_1_31") (pintype "power_in"))
      (node (ref "U1") (pin "47") (pinfunction "VSS_2_47") (pintype "power_in"))
      (node (ref "U1") (pin "63") (pinfunction "VSS_3_63") (pintype "power_in"))
      (node (ref "U2") (pin "2") (pinfunction "VSS_2") (pintype "power_in"))
      (node (ref "U3") (pin "2") (pinfunction "GND_2") (pintype "power_in"))
      (node (ref "U4") (pin "4") (pinfunction "AGND_4") (pintype "bidirectional"))
      (node (ref "U4") (pin "8") (pinfunction "PGND_8") (pintype "bidirectional"))
      (node (ref "U5") (pin "5") (pinfunction "GND_5") (pintype "bidirectional"))
      (node (ref "U6") (pin "1") (pinfunction "GND_1") (pintype "bidirectional"))
      (node (ref "U6") (pin "31") (pinfunction "GND_31") (pintype "bidirectional"))
      (node (ref "U6") (pin "35") (pinfunction "GND_35") (pintype "bidirectional"))
      (node (ref "U6") (pin "36") (pinfunction "GND_36") (pintype "bidirectional"))
      (node (ref "U6") (pin "37") (pinfunction "GND_37") (pintype "bidirectional"))
      (node (ref "U6") (pin "38") (pinfunction "GND_38") (pintype "bidirectional"))
      (node (ref "U6") (pin "40") (pinfunction "GND_40") (pintype "bidirectional"))
      (node (ref "U6") (pin "45") (pinfunction "GND_45") (pintype "bidirectional"))
      (node (ref "U6") (pin "48") (pinfunction "GND_48") (pintype "bidirectional"))
      (node (ref "U6") (pin "50") (pinfunction "GND_50") (pintype "bidirectional"))
      (node (ref "U7") (pin "1") (pinfunction "GND_1") (pintype "power_in"))
      (node (ref "U8") (pin "2") (pinfunction "GND_2") (pintype "power_in"))
      (node (ref "USART1") (pin "1") (pinfunction "1_1") (pintype "passive"))
    )
    (net (code "16") (name "I2C1_SCL") (class "Default")
      (node (ref "I2C1") (pin "3") (pinfunction "3_3") (pintype "passive"))
      (node (ref "R29") (pin "2") (pinfunction "2_2") (pintype "passive"))
      (node (ref "U1") (pin "61") (pinfunction "PB8_61") (pintype "bidirectional"))
    )
    (net (code "17") (name "I2C1_SDA") (class "Default")
      (node (ref "I2C1") (pin "2") (pinfunction "2_2") (pintype "passive"))
      (node (ref "R30") (pin "2") (pinfunction "2_2") (pintype "passive"))
      (node (ref "U1") (pin "62") (pinfunction "PB9_62") (pintype "bidirectional"))
    )
    (net (code "18") (name "JNTRST") (class "Default")
      (node (ref "DIGITAL") (pin "3") (pinfunction "3_3") (pintype "passive"))
      (node (ref "U1") (pin "56") (pinfunction "PB4_56") (pintype "bidirectional"))
    )
    (net (code "19") (name "JTCK{slash}SWCLK") (class "Default")
      (node (ref "SWD") (pin "4") (pinfunction "4_4") (pintype "passive"))
      (node (ref "U1") (pin "49") (pinfunction "PA14_49") (pintype "bidirectional"))
    )
    (net (code "20") (name "JTDI") (class "Default")
      (node (ref "U1") (pin "50") (pinfunction "PA15_50") (pintype "bidirectional"))
    )
    (net (code "21") (name "JTDO{slash}SWO") (class "Default")
      (node (ref "SWD") (pin "1") (pinfunction "1_1") (pintype "passive"))
      (node (ref "U1") (pin "55") (pinfunction "PB3_55") (pintype "bidirectional"))
    )
    (net (code "22") (name "JTMS{slash}SWDIO") (class "Default")
      (node (ref "SWD") (pin "6") (pinfunction "6_6") (pintype "passive"))
      (node (ref "U1") (pin "46") (pinfunction "PA13_46") (pintype "bidirectional"))
    )
    (net (code "23") (name "NETLIGHT") (class "Default")
      (node (ref "R26") (pin "2") (pinfunction "2_2") (pintype "passive"))
      (node (ref "U6") (pin "13") (pinfunction "NETLIGHT_13") (pintype "bidirectional"))
    )
    (net (code "24") (name "NRST") (class "Default")
      (node (ref "C9") (pin "1") (pinfunction "1_1") (pintype "passive"))
      (node (ref "S2") (pin "3") (pinfunction "2_3") (pintype "passive"))
      (node (ref "SWD") (pin "2") (pinfunction "2_2") (pintype "passive"))
      (node (ref "U1") (pin "7") (pinfunction "NRST_7") (pintype "bidirectional"))
    )
    (net (code "25") (name "Net-(BOOT-Pad3)") (class "Default")
      (node (ref "BOOT") (pin "3") (pinfunction "3_3") (pintype "passive"))
      (node (ref "R7") (pin "1") (pinfunction "1_1") (pintype "passive"))
    )
    (net (code "26") (name "Net-(BOOT-Pad4)") (class "Default")
      (node (ref "BOOT") (pin "4") (pinfunction "4_4") (pintype "passive"))
      (node (ref "R8") (pin "2") (pinfunction "2_2") (pintype "passive"))
    )
    (net (code "27") (name "Net-(C1-Pad1)") (class "Default")
      (node (ref "C1") (pin "1") (pinfunction "1_1") (pintype "passive"))
      (node (ref "R3") (pin "1") (pinfunction "1_1") (pintype "passive"))
    )
    (net (code "28") (name "Net-(C11-Pad1)") (class "Default")
      (node (ref "C11") (pin "1") (pinfunction "1_1") (pintype "passive"))
      (node (ref "R10") (pin "1") (pinfunction "1_1") (pintype "passive"))
      (node (ref "X1") (pin "P$1") (pinfunction "P$1_P$1") (pintype "bidirectional"))
    )
    (net (code "29") (name "Net-(C13-Pad1)") (class "Default")
      (node (ref "C13") (pin "1") (pinfunction "1_1") (pintype "passive"))
      (node (ref "Q1") (pin "1") (pinfunction "1_1") (pintype "passive"))
      (node (ref "R9") (pin "1") (pinfunction "1_1") (pintype "passive"))
    )
    (net (code "30") (name "Net-(C31-Pad2)") (class "Default")
      (node (ref "C31") (pin "2") (pinfunction "2_2") (pintype "passive"))
      (node (ref "R25") (pin "1") (pinfunction "1_1") (pintype "passive"))
      (node (ref "RF_ANT") (pin "D") (pinfunction "D_D") (pintype "bidirectional"))
    )
    (net (code "31") (name "Net-(CHG-PadC)") (class "Default")
      (node (ref "CHG") (pin "C") (pinfunction "C_C") (pintype "passive"))
      (node (ref "R11") (pin "2") (pinfunction "2_2") (pintype "passive"))
    )
    (net (code "32") (name "Net-(L2-2)") (class "Default")
      (node (ref "L2") (pin "P$2") (pinfunction "2_P$2") (pintype "passive"))
      (node (ref "U4") (pin "1") (pinfunction "LX_1") (pintype "bidirectional"))
    )
    (net (code "33") (name "Net-(LED-PadC)") (class "Default")
      (node (ref "LED") (pin "C") (pinfunction "C_C") (pintype "passive"))
      (node (ref "R2") (pin "2") (pinfunction "2_2") (pintype "passive"))
    )
    (net (code "34") (name "Net-(MODEMCTL-Pad8)") (class "Default")
      (node (ref "MODEMCTL") (pin "8") (pinfunction "8_8") (pintype "passive"))
      (node (ref "R32") (pin "2") (pinfunction "2_2") (pintype "passive"))
    )
    (net (code "35") (name "Net-(MODEMCTL-Pad10)") (class "Default")
      (node (ref "MODEMCTL") (pin "10") (pinfunction "10_10") (pintype "passive"))
      (node (ref "R5") (pin "2") (pinfunction "2_2") (pintype "passive"))
    )
    (net (code "36") (name "Net-(NET-PadC)") (class "Default")
      (node (ref "NET") (pin "C") (pinfunction "C_C") (pintype "passive"))
      (node (ref "R28") (pin "1") (pinfunction "1_1") (pintype "passive"))
    )
    (net (code "37") (name "Net-(PWR-PadA)") (class "Default")
      (node (ref "PWR") (pin "A") (pinfunction "A_A") (pintype "passive"))
      (node (ref "R1") (pin "1") (pinfunction "1_1") (pintype "passive"))
    )
    (net (code "38") (name "Net-(Q2-B)") (class "Default")
      (node (ref "Q2") (pin "1") (pinfunction "B_1") (pintype "passive"))
      (node (ref "R33") (pin "1") (pinfunction "1_1") (pintype "passive"))
      (node (ref "R34") (pin "1") (pinfunction "1_1") (pintype "passive"))
    )
    (net (code "39") (name "Net-(Q3-B)") (class "Default")
      (node (ref "Q3") (pin "1") (pinfunction "B_1") (pintype "passive"))
      (node (ref "R19") (pin "1") (pinfunction "1_1") (pintype "passive"))
      (node (ref "R22") (pin "1") (pinfunction "1_1") (pintype "passive"))
    )
    (net (code "40") (name "Net-(Q4-B)") (class "Default")
      (node (ref "Q4") (pin "1") (pinfunction "B_1") (pintype "passive"))
      (node (ref "R20") (pin "1") (pinfunction "1_1") (pintype "passive"))
      (node (ref "R23") (pin "1") (pinfunction "1_1") (pintype "passive"))
    )
    (net (code "41") (name "Net-(Q5-B)") (class "Default")
      (node (ref "Q5") (pin "1") (pinfunction "B_1") (pintype "passive"))
      (node (ref "R26") (pin "1") (pinfunction "1_1") (pintype "passive"))
      (node (ref "R27") (pin "2") (pinfunction "2_2") (pintype "passive"))
    )
    (net (code "42") (name "Net-(Q5-C)") (class "Default")
      (node (ref "Q5") (pin "3") (pinfunction "C_3") (pintype "passive"))
      (node (ref "R28") (pin "2") (pinfunction "2_2") (pintype "passive"))
    )
    (net (code "43") (name "Net-(S1-O)") (class "Default")
      (node (ref "JP4") (pin "2") (pinfunction "2_2") (pintype "passive"))
      (node (ref "S1") (pin "1") (pinfunction "O_1") (pintype "passive"))
      (node (ref "S1") (pin "2") (pinfunction "P_2") (pintype "passive"))
    )
    (net (code "44") (name "Net-(U2-PROG)") (class "Default")
      (node (ref "R13") (pin "1") (pinfunction "1_1") (pintype "passive"))
      (node (ref "U2") (pin "5") (pinfunction "PROG_5") (pintype "input"))
    )
    (net (code "45") (name "Net-(U2-STAT)") (class "Default")
      (node (ref "R11") (pin "1") (pinfunction "1_1") (pintype "passive"))
      (node (ref "U2") (pin "1") (pinfunction "STAT_1") (pintype "output"))
    )
    (net (code "46") (name "Net-(U3-EN)") (class "Default")
      (node (ref "R12") (pin "1") (pinfunction "1_1") (pintype "passive"))
      (node (ref "U3") (pin "3") (pinfunction "EN_3") (pintype "input"))
    )
    (net (code "47") (name "Net-(U4-EN)") (class "Default")
      (node (ref "R14") (pin "2") (pinfunction "2_2") (pintype "passive"))
      (node (ref "U4") (pin "2") (pinfunction "EN_2") (pintype "bidirectional"))
    )
    (net (code "48") (name "Net-(U4-FB)") (class "Default")
      (node (ref "R15") (pin "2") (pinfunction "2_2") (pintype "passive"))
      (node (ref "R16") (pin "1") (pinfunction "1_1") (pintype "passive"))
      (node (ref "U4") (pin "5") (pinfunction "FB_5") (pintype "bidirectional"))
    )
    (net (code "49") (name "OSC32_IN") (class "Default")
      (node (ref "C12") (pin "1") (pinfunction "1_1") (pintype "passive"))
      (node (ref "Q1") (pin "2") (pinfunction "2_2") (pintype "passive"))
      (node (ref "U1") (pin "3") (pinfunction "PC14-OSC32_IN_3") (pintype "bidirectional"))
    )
    (net (code "50") (name "OSC32_OUT") (class "Default")
      (node (ref "R9") (pin "2") (pinfunction "2_2") (pintype "passive"))
      (node (ref "U1") (pin "4") (pinfunction "PC15-OSC32_OUT_4") (pintype "bidirectional"))
    )
    (net (code "51") (name "OSC_IN") (class "Default")
      (node (ref "C10") (pin "1") (pinfunction "1_1") (pintype "passive"))
      (node (ref "U1") (pin "5") (pinfunction "OSC_IN_5") (pintype "input"))
      (node (ref "X1") (pin "P$2") (pinfunction "P$2_P$2") (pintype "bidirectional"))
    )
    (net (code "52") (name "OSC_OUT") (class "Default")
      (node (ref "R10") (pin "2") (pinfunction "2_2") (pintype "passive"))
      (node (ref "U1") (pin "6") (pinfunction "OSC_OUT_6") (pintype "output"))
    )
    (net (code "53") (name "PA0") (class "Default")
      (node (ref "ANALOG") (pin "6") (pinfunction "6_6") (pintype "passive"))
      (node (ref "U1") (pin "14") (pinfunction "PA0-WKUP_14") (pintype "bidirectional"))
    )
    (net (code "54") (name "PA1") (class "Default")
      (node (ref "ANALOG") (pin "5") (pinfunction "5_5") (pintype "passive"))
      (node (ref "U1") (pin "15") (pinfunction "PA1_15") (pintype "bidirectional"))
    )
    (net (code "55") (name "PA2") (class "Default")
      (node (ref "DIGITAL") (pin "8") (pinfunction "8_8") (pintype "passive"))
      (node (ref "U1") (pin "16") (pinfunction "PA2_16") (pintype "bidirectional"))
    )
    (net (code "56") (name "PA3") (class "Default")
      (node (ref "DIGITAL") (pin "7") (pinfunction "7_7") (pintype "passive"))
      (node (ref "U1") (pin "17") (pinfunction "PA3_17") (pintype "bidirectional"))
    )
    (net (code "57") (name "PA4") (class "Default")
      (node (ref "CC1101") (pin "4") (pinfunction "4_4") (pintype "passive"))
      (node (ref "SPI1") (pin "5") (pinfunction "5_5") (pintype "passive"))
      (node (ref "U1") (pin "20") (pinfunction "PA4_20") (pintype "bidirectional"))
    )
    (net (code "58") (name "PA5") (class "Default")
      (node (ref "CC1101") (pin "7") (pinfunction "7_7") (pintype "passive"))
      (node (ref "SPI1") (pin "2") (pinfunction "2_2") (pintype "passive"))
      (node (ref "U1") (pin "21") (pinfunction "PA5_21") (pintype "bidirectional"))
    )
    (net (code "59") (name "PA6") (class "Default")
      (node (ref "CC1101") (pin "8") (pinfunction "8_8") (pintype "passive"))
      (node (ref "SPI1") (pin "3") (pinfunction "3_3") (pintype "passive"))
      (node (ref "U1") (pin "22") (pinfunction "PA6_22") (pintype "bidirectional"))
    )
    (net (code "60") (name "PA7") (class "Default")
      (node (ref "CC1101") (pin "6") (pinfunction "6_6") (pintype "passive"))
      (node (ref "SPI1") (pin "4") (pinfunction "4_4") (pintype "passive"))
      (node (ref "U1") (pin "23") (pinfunction "PA7_23") (pintype "bidirectional"))
    )
    (net (code "61") (name "PA8") (class "Default")
      (node (ref "DIGITAL") (pin "1") (pinfunction "1_1") (pintype "passive"))
      (node (ref "U1") (pin "41") (pinfunction "PA8_41") (pintype "bidirectional"))
    )
    (net (code "62") (name "PB0") (class "Default")
      (node (ref "ANALOG") (pin "4") (pinfunction "4_4") (pintype "passive"))
      (node (ref "U1") (pin "26") (pinfunction "PB0_26") (pintype "bidirectional"))
    )
    (net (code "63") (name "PB5") (class "Default")
      (node (ref "DIGITAL") (pin "4") (pinfunction "4_4") (pintype "passive"))
      (node (ref "U1") (pin "57") (pinfunction "PB5_57") (pintype "bidirectional"))
    )
    (net (code "64") (name "PB6") (class "Default")
      (node (ref "DIGITAL") (pin "6") (pinfunction "6_6") (pintype "passive"))
      (node (ref "U1") (pin "58") (pinfunction "PB6_58") (pintype "bidirectional"))
    )
    (net (code "65") (name "PB12") (class "Default")
      (node (ref "CC1101") (pin "5") (pinfunction "5_5") (pintype "passive"))
      (node (ref "SPI2") (pin "2") (pinfunction "2_2") (pintype "passive"))
      (node (ref "U1") (pin "33") (pinfunction "PB12_33") (pintype "bidirectional"))
    )
    (net (code "66") (name "PB13") (class "Default")
      (node (ref "LED") (pin "A") (pinfunction "A_A") (pintype "passive"))
      (node (ref "SPI2") (pin "5") (pinfunction "5_5") (pintype "passive"))
      (node (ref "U1") (pin "34") (pinfunction "PB13_34") (pintype "bidirectional"))
    )
    (net (code "67") (name "PB14") (class "Default")
      (node (ref "SPI2") (pin "4") (pinfunction "4_4") (pintype "passive"))
      (node (ref "U1") (pin "35") (pinfunction "PB14_35") (pintype "bidirectional"))
    )
    (net (code "68") (name "PB15") (class "Default")
      (node (ref "SPI2") (pin "3") (pinfunction "3_3") (pintype "passive"))
      (node (ref "U1") (pin "36") (pinfunction "PB15_36") (pintype "bidirectional"))
    )
    (net (code "69") (name "PC0") (class "Default")
      (node (ref "ANALOG") (pin "1") (pinfunction "1_1") (pintype "passive"))
      (node (ref "U1") (pin "8") (pinfunction "PC0_8") (pintype "bidirectional"))
    )
    (net (code "70") (name "PC1") (class "Default")
      (node (ref "ANALOG") (pin "2") (pinfunction "2_2") (pintype "passive"))
      (node (ref "U1") (pin "9") (pinfunction "PC1_9") (pintype "bidirectional"))
    )
    (net (code "71") (name "PC3") (class "Default")
      (node (ref "ANALOG") (pin "3") (pinfunction "3_3") (pintype "passive"))
      (node (ref "U1") (pin "11") (pinfunction "PC3_11") (pintype "bidirectional"))
    )
    (net (code "72") (name "PC6") (class "Default")
      (node (ref "JP2") (pin "2") (pinfunction "2_2") (pintype "passive"))
      (node (ref "U1") (pin "37") (pinfunction "PC6_37") (pintype "bidirectional"))
    )
    (net (code "73") (name "PC7") (class "Default")
      (node (ref "JP2") (pin "3") (pinfunction "3_3") (pintype "passive"))
      (node (ref "U1") (pin "38") (pinfunction "PC7_38") (pintype "bidirectional"))
    )
    (net (code "74") (name "PC8") (class "Default")
      (node (ref "JP2") (pin "4") (pinfunction "4_4") (pintype "passive"))
      (node (ref "U1") (pin "39") (pinfunction "PC8_39") (pintype "bidirectional"))
    )
    (net (code "75") (name "PC9") (class "Default")
      (node (ref "JP2") (pin "5") (pinfunction "5_5") (pintype "passive"))
      (node (ref "U1") (pin "40") (pinfunction "PC9_40") (pintype "bidirectional"))
    )
    (net (code "76") (name "PC11") (class "Default")
      (node (ref "DIGITAL") (pin "5") (pinfunction "5_5") (pintype "passive"))
      (node (ref "U1") (pin "52") (pinfunction "PC11_52") (pintype "bidirectional"))
    )
    (net (code "77") (name "PC12") (class "Default")
      (node (ref "DIGITAL") (pin "2") (pinfunction "2_2") (pintype "passive"))
      (node (ref "U1") (pin "53") (pinfunction "PC12_53") (pintype "bidirectional"))
    )
    (net (code "78") (name "PC13") (class "Default")
      (node (ref "C1") (pin "2") (pinfunction "2_2") (pintype "passive"))
      (node (ref "R4") (pin "2") (pinfunction "2_2") (pintype "passive"))
      (node (ref "S4") (pin "3") (pinfunction "2_3") (pintype "passive"))
      (node (ref "U1") (pin "2") (pinfunction "PC13_2") (pintype "bidirectional"))
    )
    (net (code "79") (name "PSM_EINT") (class "Default")
      (node (ref "MODEMCTL") (pin "2") (pinfunction "2_2") (pintype "passive"))
      (node (ref "R34") (pin "2") (pinfunction "2_2") (pintype "passive"))
    )
    (net (code "80") (name "RF_ANT") (class "Default")
      (node (ref "C29") (pin "2") (pinfunction "2_2") (pintype "passive"))
      (node (ref "R25") (pin "2") (pinfunction "2_2") (pintype "passive"))
      (node (ref "U6") (pin "39") (pinfunction "RF_ANT_39") (pintype "bidirectional"))
    )
    (net (code "81") (name "SIM1_CLK") (class "Default")
      (node (ref "D3") (pin "5") (pinfunction "C4_5") (pintype "passive"))
      (node (ref "R18") (pin "2") (pinfunction "2_2") (pintype "passive"))
      (node (ref "U6") (pin "30") (pinfunction "SIM1_CLK_30") (pintype "bidirectional"))
    )
    (net (code "82") (name "SIM1_CLK_CONN") (class "Default")
      (node (ref "C26") (pin "1") (pinfunction "1_1") (pintype "passive"))
      (node (ref "R18") (pin "1") (pinfunction "1_1") (pintype "passive"))
      (node (ref "U5") (pin "3") (pinfunction "CLK_3") (pintype "bidirectional"))
      (node (ref "U7") (pin "6") (pinfunction "CLK_6") (pintype "input"))
    )
    (net (code "83") (name "SIM1_DATA") (class "Default")
      (node (ref "D3") (pin "4") (pinfunction "C3_4") (pintype "passive"))
      (node (ref "R21") (pin "2") (pinfunction "2_2") (pintype "passive"))
      (node (ref "R24") (pin "2") (pinfunction "2_2") (pintype "passive"))
      (node (ref "U6") (pin "29") (pinfunction "SIM1_DATA_29") (pintype "bidirectional"))
    )
    (net (code "84") (name "SIM1_DATA_CONN") (class "Default")
      (node (ref "C27") (pin "2") (pinfunction "2_2") (pintype "passive"))
      (node (ref "R24") (pin "1") (pinfunction "1_1") (pintype "passive"))
      (node (ref "U5") (pin "7") (pinfunction "I/O_7") (pintype "bidirectional"))
      (node (ref "U7") (pin "3") (pinfunction "I/O_3") (pintype "bidirectional"))
    )
    (net (code "85") (name "SIM1_RST") (class "Default")
      (node (ref "D3") (pin "3") (pinfunction "C2_3") (pintype "passive"))
      (node (ref "R17") (pin "2") (pinfunction "2_2") (pintype "passive"))
      (node (ref "U6") (pin "28") (pinfunction "SIM1_RST_28") (pintype "bidirectional"))
    )
    (net (code "86") (name "SIM1_RST_CONN") (class "Default")
      (node (ref "C24") (pin "2") (pinfunction "2_2") (pintype "passive"))
      (node (ref "R17") (pin "1") (pinfunction "1_1") (pintype "passive"))
      (node (ref "U5") (pin "2") (pinfunction "RST_2") (pintype "bidirectional"))
      (node (ref "U7") (pin "7") (pinfunction "RST_7") (pintype "input"))
    )
    (net (code "87") (name "SIM1_VDD") (class "Default")
      (node (ref "C25") (pin "1") (pinfunction "1_1") (pintype "passive"))
      (node (ref "D3") (pin "1") (pinfunction "C1_1") (pintype "passive"))
      (node (ref "R21") (pin "1") (pinfunction "1_1") (pintype "passive"))
      (node (ref "U5") (pin "1") (pinfunction "VCC_1") (pintype "bidirectional"))
      (node (ref "U6") (pin "27") (pinfunction "SIM1_VDD_27") (pintype "bidirectional"))
      (node (ref "U7") (pin "8") (pinfunction "VCC_8") (pintype "power_in"))
    )
    (net (code "88") (name "STM_PSM_EINT") (class "Default")
      (node (ref "MODEMCTL") (pin "1") (pinfunction "1_1") (pintype "passive"))
      (node (ref "U1") (pin "24") (pinfunction "PC4_24") (pintype "bidirectional"))
    )
    (net (code "89") (name "STM_PWRKEY") (class "Default")
      (node (ref "MODEMCTL") (pin "3") (pinfunction "3_3") (pintype "passive"))
      (node (ref "U1") (pin "25") (pinfunction "PC5_25") (pintype "bidirectional"))
    )
    (net (code "90") (name "STM_RESET") (class "Default")
      (node (ref "MODEMCTL") (pin "5") (pinfunction "5_5") (pintype "passive"))
      (node (ref "U1") (pin "27") (pinfunction "PB1_27") (pintype "bidirectional"))
    )
    (net (code "91") (name "STM_RX") (class "Default")
      (node (ref "MODEMCTL") (pin "7") (pinfunction "7_7") (pintype "passive"))
      (node (ref "U1") (pin "30") (pinfunction "PB11_30") (pintype "bidirectional"))
    )
    (net (code "92") (name "STM_TX") (class "Default")
      (node (ref "MODEMCTL") (pin "9") (pinfunction "9_9") (pintype "passive"))
      (node (ref "U1") (pin "29") (pinfunction "PB10_29") (pintype "bidirectional"))
    )
    (net (code "93") (name "USART1_RX") (class "Default")
      (node (ref "U1") (pin "43") (pinfunction "PA10_43") (pintype "bidirectional"))
      (node (ref "USART1") (pin "2") (pinfunction "2_2") (pintype "passive"))
    )
    (net (code "94") (name "USART1_TX") (class "Default")
      (node (ref "U1") (pin "42") (pinfunction "PA9_42") (pintype "bidirectional"))
      (node (ref "USART1") (pin "3") (pinfunction "3_3") (pintype "passive"))
    )
    (net (code "95") (name "USB_CONN_D_N") (class "Default")
      (node (ref "POWER") (pin "D-") (pinfunction "D-_D-") (pintype "bidirectional"))
      (node (ref "U8") (pin "1") (pinfunction "I/O1_2_1") (pintype "bidirectional"))
    )
    (net (code "96") (name "USB_CONN_D_P") (class "Default")
      (node (ref "POWER") (pin "D+") (pinfunction "D+_D+") (pintype "bidirectional"))
      (node (ref "U8") (pin "3") (pinfunction "I/O2_2_3") (pintype "bidirectional"))
    )
    (net (code "97") (name "USB_D_N") (class "Default")
      (node (ref "CAN") (pin "3") (pinfunction "3_3") (pintype "passive"))
      (node (ref "U1") (pin "44") (pinfunction "PA11_44") (pintype "bidirectional"))
      (node (ref "U8") (pin "6") (pinfunction "I/O1_6") (pintype "bidirectional"))
    )
    (net (code "98") (name "USB_D_P") (class "Default")
      (node (ref "CAN") (pin "2") (pinfunction "2_2") (pintype "passive"))
      (node (ref "R31") (pin "2") (pinfunction "2_2") (pintype "passive"))
      (node (ref "U1") (pin "45") (pinfunction "PA12_45") (pintype "bidirectional"))
      (node (ref "U8") (pin "4") (pinfunction "I/O2_4") (pintype "bidirectional"))
    )
    (net (code "99") (name "V+") (class "Default")
      (node (ref "C15") (pin "2") (pinfunction "2_2") (pintype "passive"))
      (node (ref "C19") (pin "+") (pinfunction "+_+") (pintype "passive"))
      (node (ref "C20") (pin "2") (pinfunction "2_2") (pintype "passive"))
      (node (ref "C30") (pin "2") (pinfunction "2_2") (pintype "passive"))
      (node (ref "C32") (pin "2") (pinfunction "2_2") (pintype "passive"))
      (node (ref "C33") (pin "2") (pinfunction "2_2") (pintype "passive"))
      (node (ref "D4") (pin "C") (pinfunction "C_C") (pintype "passive"))
      (node (ref "L2") (pin "P$1") (pinfunction "1_P$1") (pintype "passive"))
      (node (ref "NET") (pin "A") (pinfunction "A_A") (pintype "passive"))
      (node (ref "R12") (pin "2") (pinfunction "2_2") (pintype "passive"))
      (node (ref "R14") (pin "1") (pinfunction "1_1") (pintype "passive"))
      (node (ref "S1") (pin "3") (pinfunction "S_3") (pintype "passive"))
      (node (ref "U3") (pin "1") (pinfunction "IN_1") (pintype "power_in"))
      (node (ref "U4") (pin "3") (pinfunction "VIN_3") (pintype "bidirectional"))
      (node (ref "U6") (pin "33") (pinfunction "VBAT_33") (pintype "bidirectional"))
      (node (ref "U6") (pin "34") (pinfunction "VBAT_34") (pintype "bidirectional"))
    )
    (net (code "100") (name "VBUS") (class "Default")
      (node (ref "C14") (pin "2") (pinfunction "2_2") (pintype "passive"))
      (node (ref "CHG") (pin "A") (pinfunction "A_A") (pintype "passive"))
      (node (ref "F1") (pin "1") (pinfunction "1_1") (pintype "passive"))
      (node (ref "POWER-PINS") (pin "4") (pinfunction "4_4") (pintype "passive"))
      (node (ref "POWER-PINS1") (pin "4") (pinfunction "4_4") (pintype "passive"))
      (node (ref "U2") (pin "4") (pinfunction "VDD_4") (pintype "power_in"))
      (node (ref "U8") (pin "5") (pinfunction "VBUS_5") (pintype "power_in"))
      (node (ref "USART1") (pin "4") (pinfunction "4_4") (pintype "passive"))
    )
    (net (code "101") (name "VDD") (class "Default")
      (node (ref "C2") (pin "2") (pinfunction "2_2") (pintype "passive"))
      (node (ref "C3") (pin "2") (pinfunction "2_2") (pintype "passive"))
      (node (ref "L1") (pin "1") (pinfunction "1_1") (pintype "passive"))
      (node (ref "U1") (pin "13") (pinfunction "VDDA_13") (pintype "power_in"))
    )
    (net (code "102") (name "VIN") (class "Default")
      (node (ref "F1") (pin "2") (pinfunction "2_2") (pintype "passive"))
      (node (ref "POWER") (pin "VBUS") (pinfunction "VBUS_VBUS") (pintype "power_in"))
      (node (ref "U$1") (pin "PWR2") (pinfunction "TIP_PWR2") (pintype "bidirectional"))
    )
    (net (code "103") (name "unconnected-(CC1101-Pad3)") (class "Default")
      (node (ref "CC1101") (pin "3") (pinfunction "3_3") (pintype "passive"))
    )
    (net (code "104") (name "unconnected-(CC1101-Pad9)") (class "Default")
      (node (ref "CC1101") (pin "9") (pinfunction "9_9") (pintype "passive"))
    )
    (net (code "105") (name "unconnected-(D3-C5-Pad6)") (class "Default")
      (node (ref "D3") (pin "6") (pinfunction "C5_6") (pintype "passive"))
    )
    (net (code "106") (name "unconnected-(POWER-PadID)") (class "Default")
      (node (ref "POWER") (pin "ID") (pinfunction "ID_ID") (pintype "bidirectional"))
    )
    (net (code "107") (name "unconnected-(U1A-PB7-Pad59)") (class "Default")
      (node (ref "U1") (pin "59") (pinfunction "PB7_59") (pintype "bidirectional"))
    )
    (net (code "108") (name "unconnected-(U1A-PC2-Pad10)") (class "Default")
      (node (ref "U1") (pin "10") (pinfunction "PC2_10") (pintype "bidirectional"))
    )
    (net (code "109") (name "unconnected-(U1A-PC10-Pad51)") (class "Default")
      (node (ref "U1") (pin "51") (pinfunction "PC10_51") (pintype "bidirectional"))
    )
    (net (code "110") (name "unconnected-(U1A-PD2-Pad54)") (class "Default")
      (node (ref "U1") (pin "54") (pinfunction "PD2_54") (pintype "bidirectional"))
    )
    (net (code "111") (name "unconnected-(U3-P4-Pad4)") (class "Default")
      (node (ref "U3") (pin "4") (pinfunction "P4_4") (pintype "bidirectional"))
    )
    (net (code "112") (name "unconnected-(U4-RSET-Pad6)") (class "Default")
      (node (ref "U4") (pin "6") (pinfunction "RSET_6") (pintype "bidirectional"))
    )
    (net (code "113") (name "unconnected-(U5-VPP-Pad6)") (class "Default")
      (node (ref "U5") (pin "6") (pinfunction "VPP_6") (pintype "bidirectional"))
    )
    (net (code "114") (name "unconnected-(U6-ADC-Pad2)") (class "Default")
      (node (ref "U6") (pin "2") (pinfunction "ADC_2") (pintype "bidirectional"))
    )
    (net (code "115") (name "unconnected-(U6-CTS-Pad23)") (class "Default")
      (node (ref "U6") (pin "23") (pinfunction "CTS_23") (pintype "bidirectional"))
    )
    (net (code "116") (name "unconnected-(U6-RESERVED-Pad3)") (class "Default")
      (node (ref "U6") (pin "3") (pinfunction "RESERVED_3") (pintype "bidirectional"))
    )
    (net (code "117") (name "unconnected-(U6-RESERVED-Pad4)") (class "Default")
      (node (ref "U6") (pin "4") (pinfunction "RESERVED_4") (pintype "bidirectional"))
    )
    (net (code "118") (name "unconnected-(U6-RESERVED-Pad5)") (class "Default")
      (node (ref "U6") (pin "5") (pinfunction "RESERVED_5") (pintype "bidirectional"))
    )
    (net (code "119") (name "unconnected-(U6-RESERVED-Pad6)") (class "Default")
      (node (ref "U6") (pin "6") (pinfunction "RESERVED_6") (pintype "bidirectional"))
    )
    (net (code "120") (name "unconnected-(U6-RESERVED-Pad7)") (class "Default")
      (node (ref "U6") (pin "7") (pinfunction "RESERVED_7") (pintype "bidirectional"))
    )
    (net (code "121") (name "unconnected-(U6-RESERVED-Pad8)") (class "Default")
      (node (ref "U6") (pin "8") (pinfunction "RESERVED_8") (pintype "bidirectional"))
    )
    (net (code "122") (name "unconnected-(U6-RESERVED-Pad9)") (class "Default")
      (node (ref "U6") (pin "9") (pinfunction "RESERVED_9") (pintype "bidirectional"))
    )
    (net (code "123") (name "unconnected-(U6-RESERVED-Pad12)") (class "Default")
      (node (ref "U6") (pin "12") (pinfunction "RESERVED_12") (pintype "bidirectional"))
    )
    (net (code "124") (name "unconnected-(U6-RESERVED-Pad32)") (class "Default")
      (node (ref "U6") (pin "32") (pinfunction "RESERVED_32") (pintype "bidirectional"))
    )
    (net (code "125") (name "unconnected-(U6-RESERVED-Pad41)") (class "Default")
      (node (ref "U6") (pin "41") (pinfunction "RESERVED_41") (pintype "bidirectional"))
    )
    (net (code "126") (name "unconnected-(U6-RESERVED-Pad42)") (class "Default")
      (node (ref "U6") (pin "42") (pinfunction "RESERVED_42") (pintype "bidirectional"))
    )
    (net (code "127") (name "unconnected-(U6-RESERVED-Pad43)") (class "Default")
      (node (ref "U6") (pin "43") (pinfunction "RESERVED_43") (pintype "bidirectional"))
    )
    (net (code "128") (name "unconnected-(U6-RESERVED-Pad44)") (class "Default")
      (node (ref "U6") (pin "44") (pinfunction "RESERVED_44") (pintype "bidirectional"))
    )
    (net (code "129") (name "unconnected-(U6-RESERVED-Pad46)") (class "Default")
      (node (ref "U6") (pin "46") (pinfunction "RESERVED_46") (pintype "bidirectional"))
    )
    (net (code "130") (name "unconnected-(U6-RESERVED-Pad47)") (class "Default")
      (node (ref "U6") (pin "47") (pinfunction "RESERVED_47") (pintype "bidirectional"))
    )
    (net (code "131") (name "unconnected-(U6-RESERVED-Pad49)") (class "Default")
      (node (ref "U6") (pin "49") (pinfunction "RESERVED_49") (pintype "bidirectional"))
    )
    (net (code "132") (name "unconnected-(U6-RI-Pad26)") (class "Default")
      (node (ref "U6") (pin "26") (pinfunction "RI_26") (pintype "bidirectional"))
    )
    (net (code "133") (name "unconnected-(U6-RTS-Pad24)") (class "Default")
      (node (ref "U6") (pin "24") (pinfunction "RTS_24") (pintype "bidirectional"))
    )
    (net (code "134") (name "unconnected-(U6-SIM2_CLK-Pad17)") (class "Default")
      (node (ref "U6") (pin "17") (pinfunction "SIM2_CLK_17") (pintype "bidirectional"))
    )
    (net (code "135") (name "unconnected-(U6-SIM2_DATA-Pad16)") (class "Default")
      (node (ref "U6") (pin "16") (pinfunction "SIM2_DATA_16") (pintype "bidirectional"))
    )
    (net (code "136") (name "unconnected-(U6-SIM2_RST-Pad25)") (class "Default")
      (node (ref "U6") (pin "25") (pinfunction "SIM2_RST_25") (pintype "bidirectional"))
    )
    (net (code "137") (name "unconnected-(U6-SIM2_VDD-Pad18)") (class "Default")
      (node (ref "U6") (pin "18") (pinfunction "SIM2_VDD_18") (pintype "bidirectional"))
    )
    (net (code "138") (name "unconnected-(U6-VDD_EXT-Pad19)") (class "Default")
      (node (ref "U6") (pin "19") (pinfunction "VDD_EXT_19") (pintype "bidirectional"))
    )
    (net (code "139") (name "unconnected-(U7-EPAD-Pad9)") (class "Default")
      (node (ref "U7") (pin "9") (pinfunction "EPAD_9") (pintype "passive"))
    )
  )
)
